# Versie_6.net
KiCad netlist of a schematic drawn in EAGLE
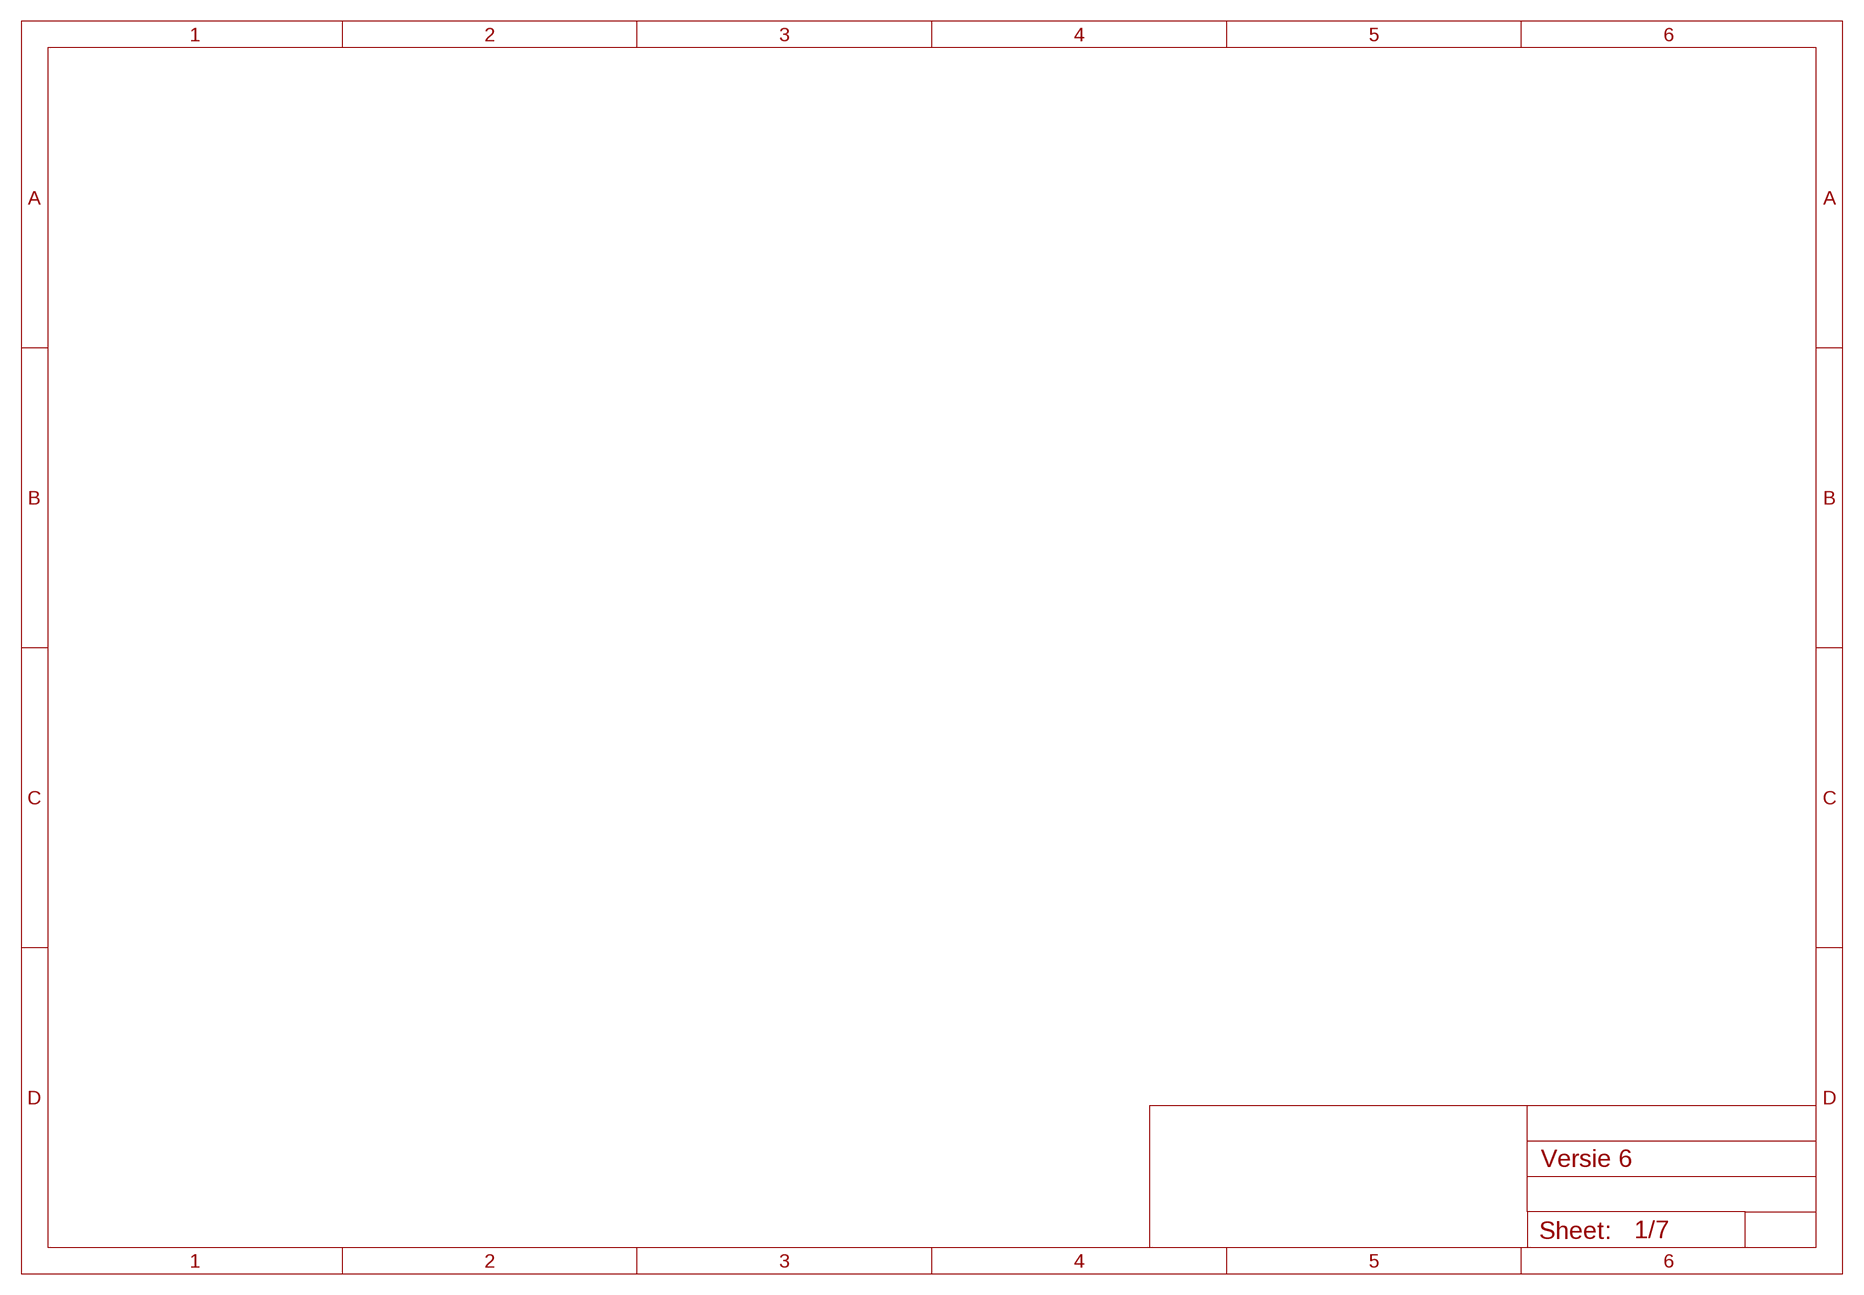
[diagram p0: schematic, sheet 1]
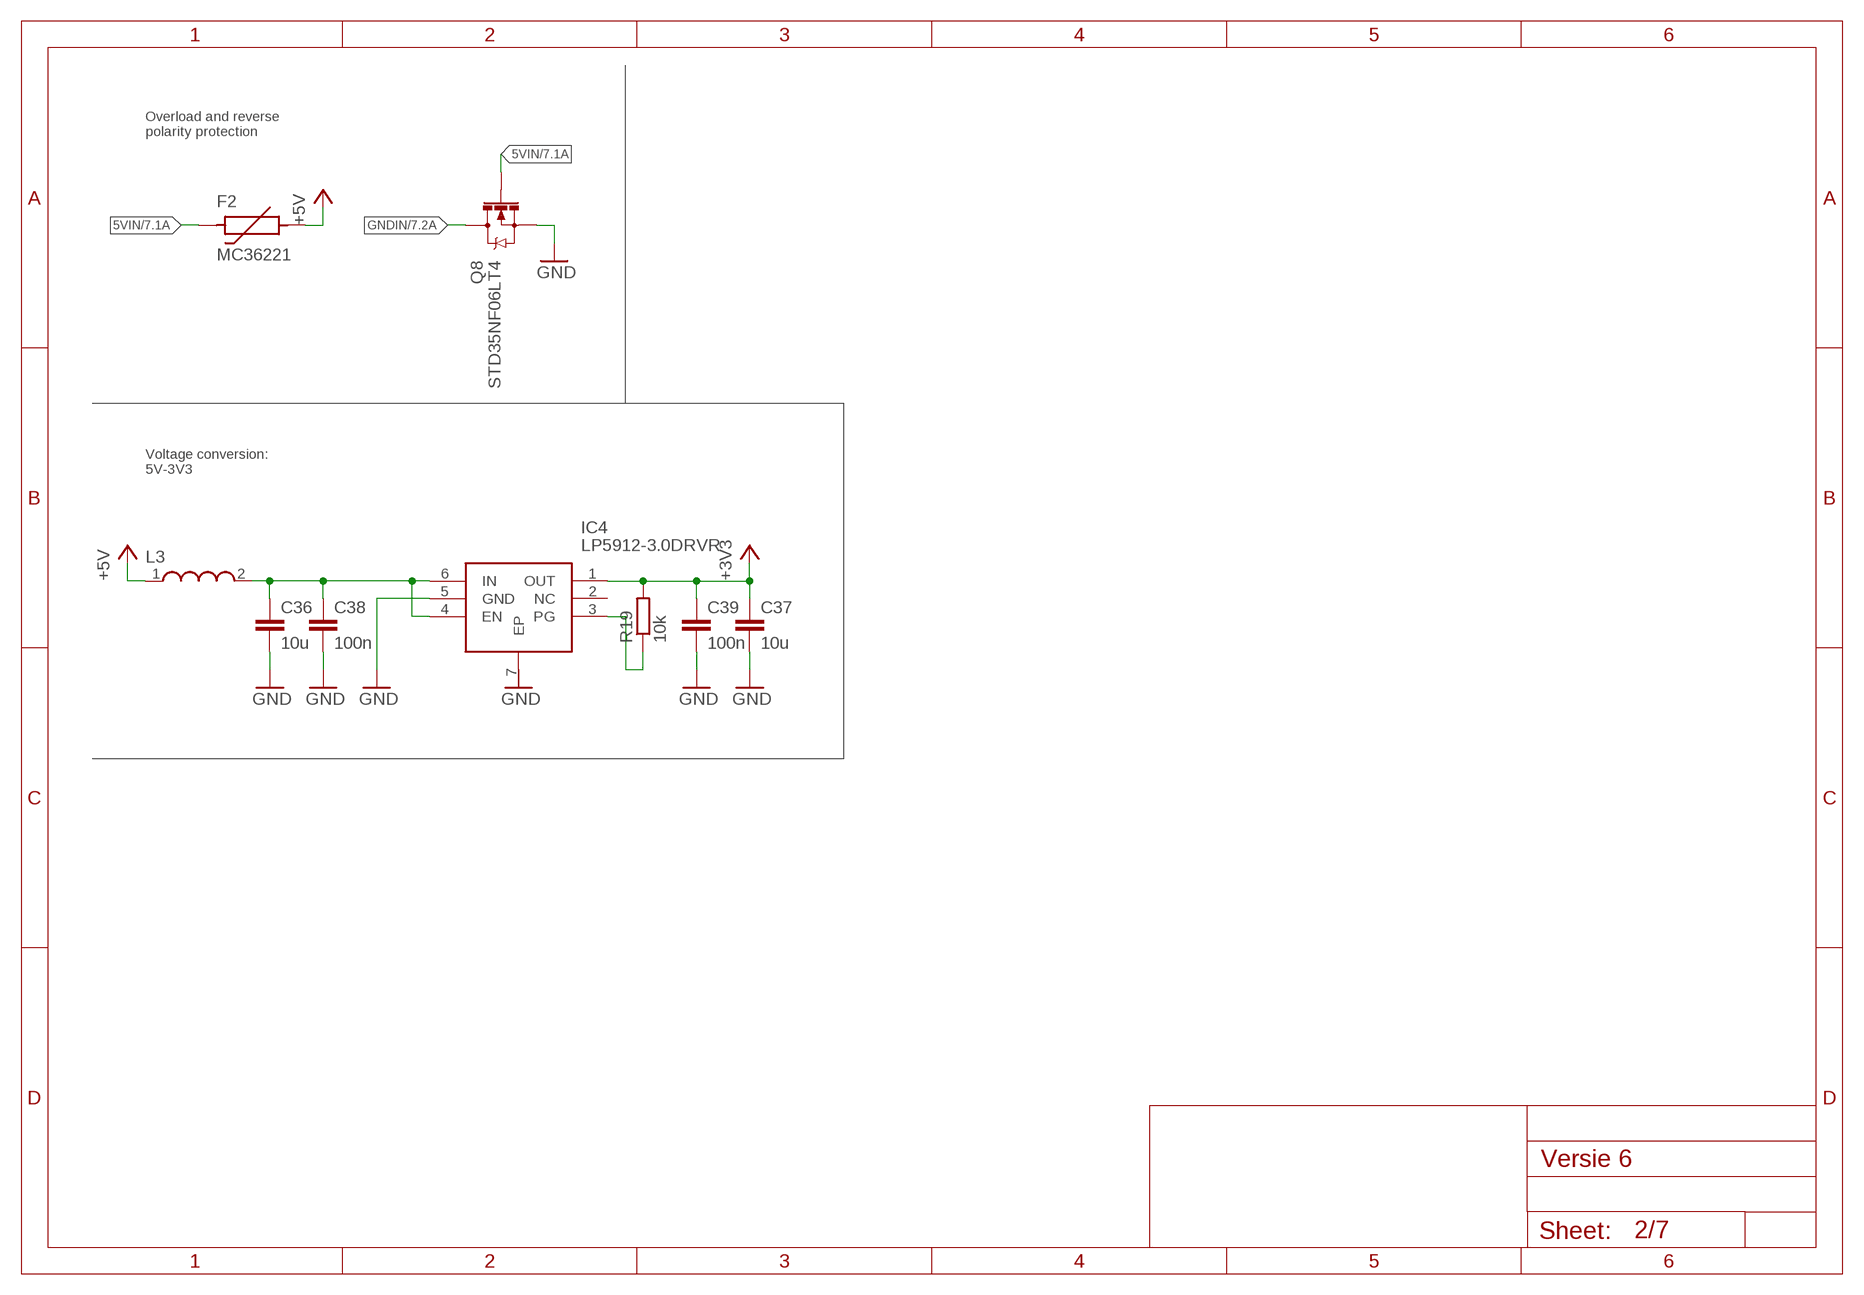
[diagram p1: schematic, sheet 2]
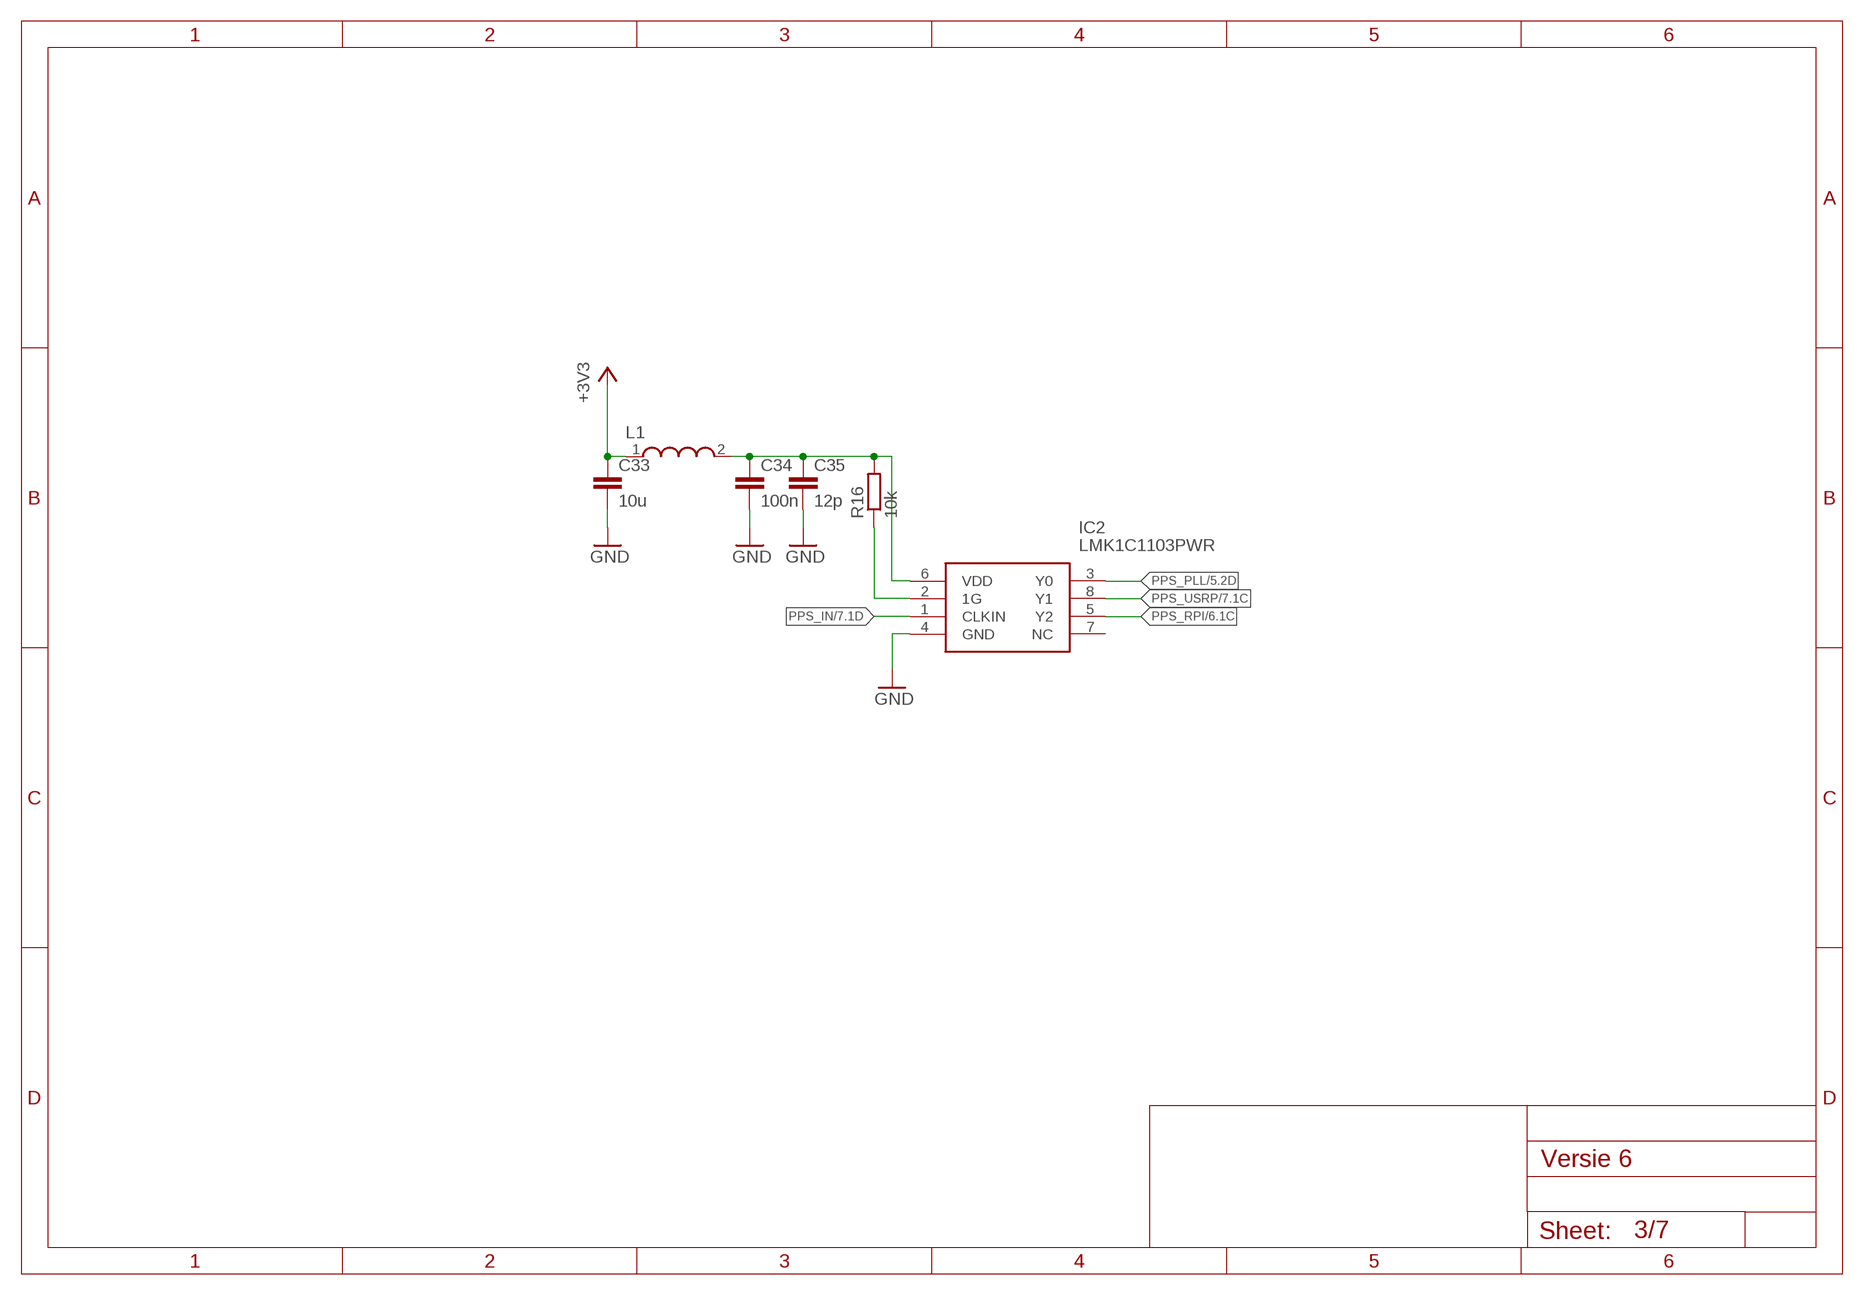
[diagram p2: schematic, sheet 3]
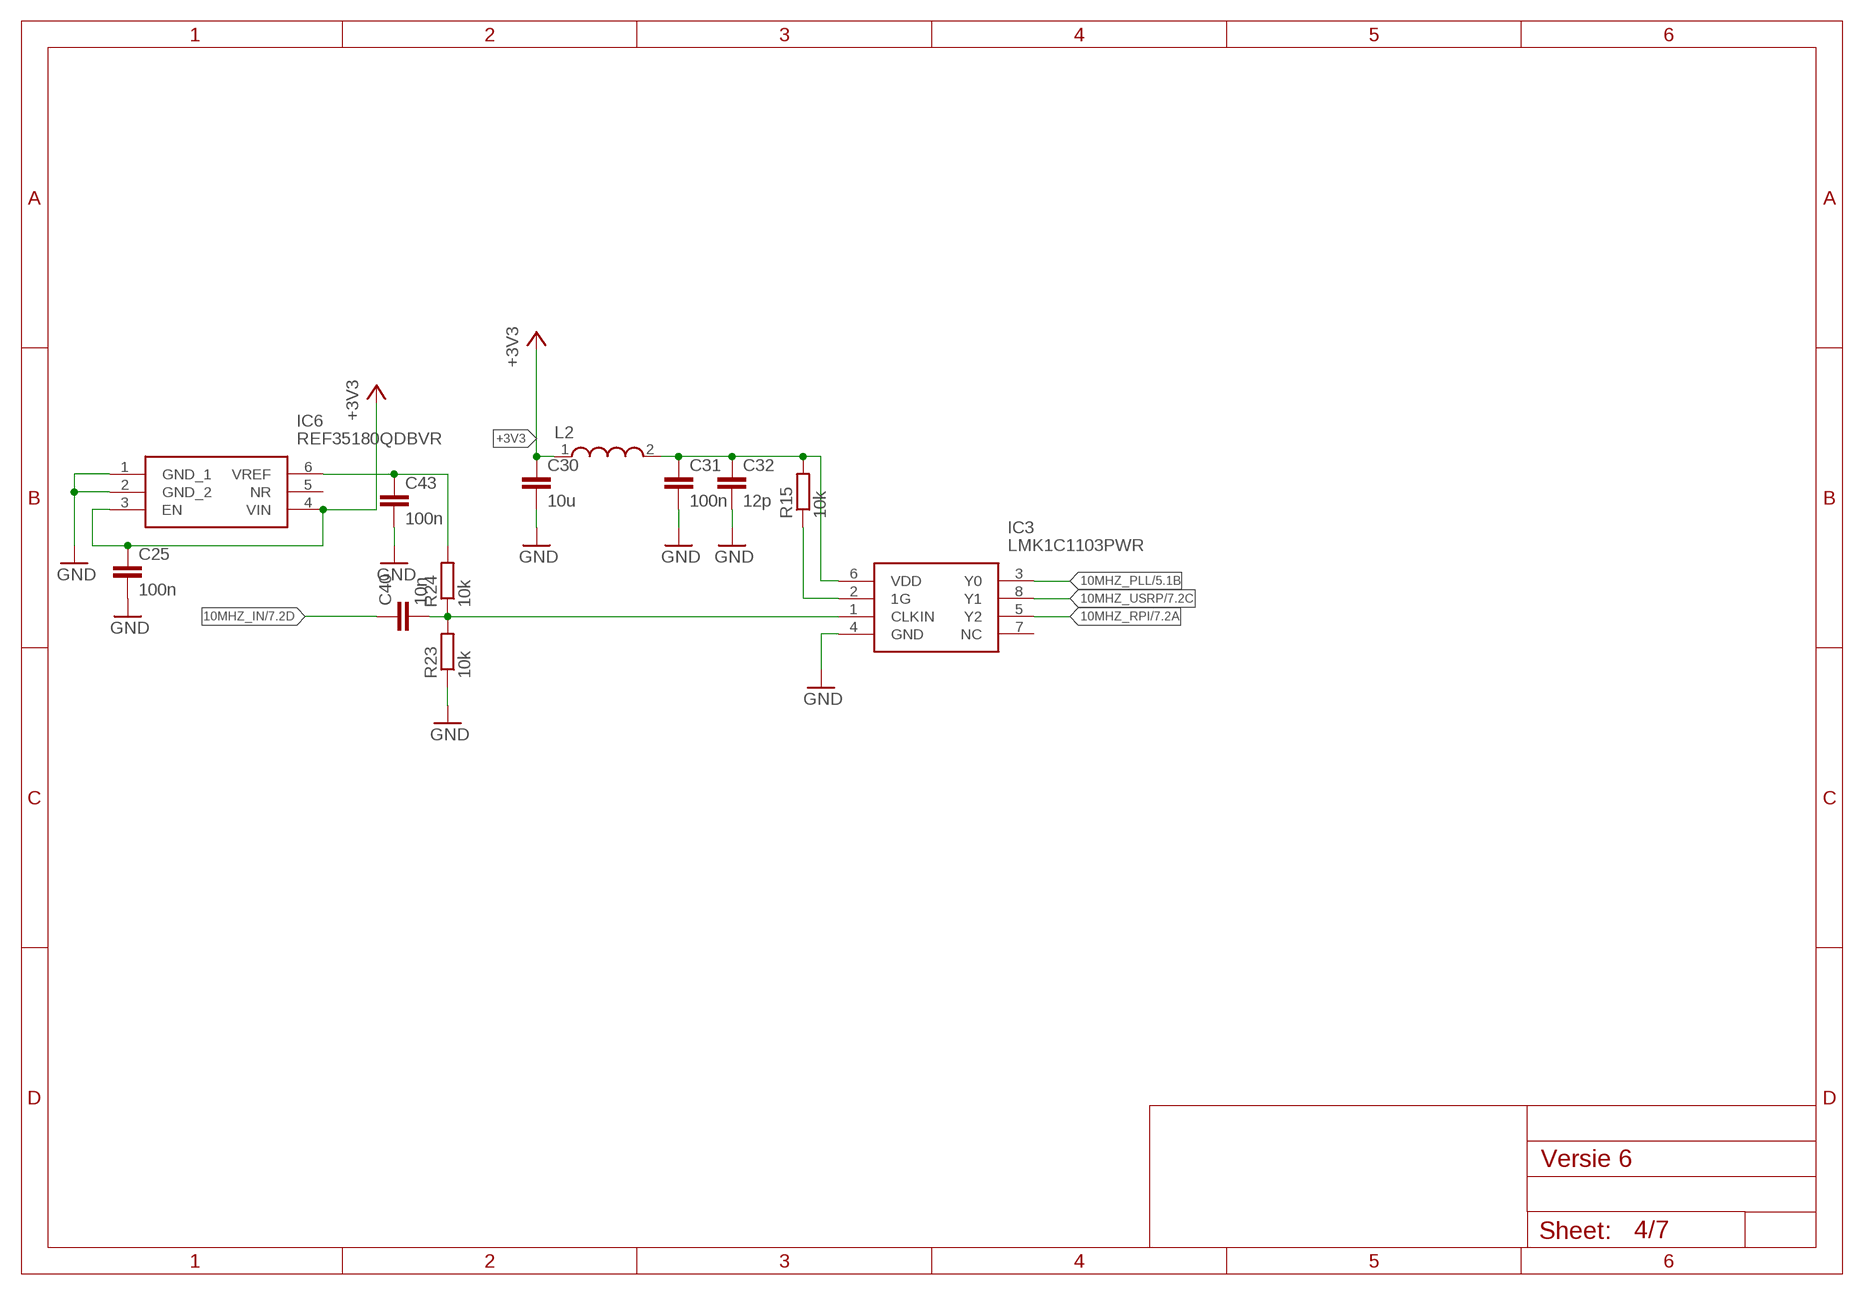
[diagram p3: schematic, sheet 4]
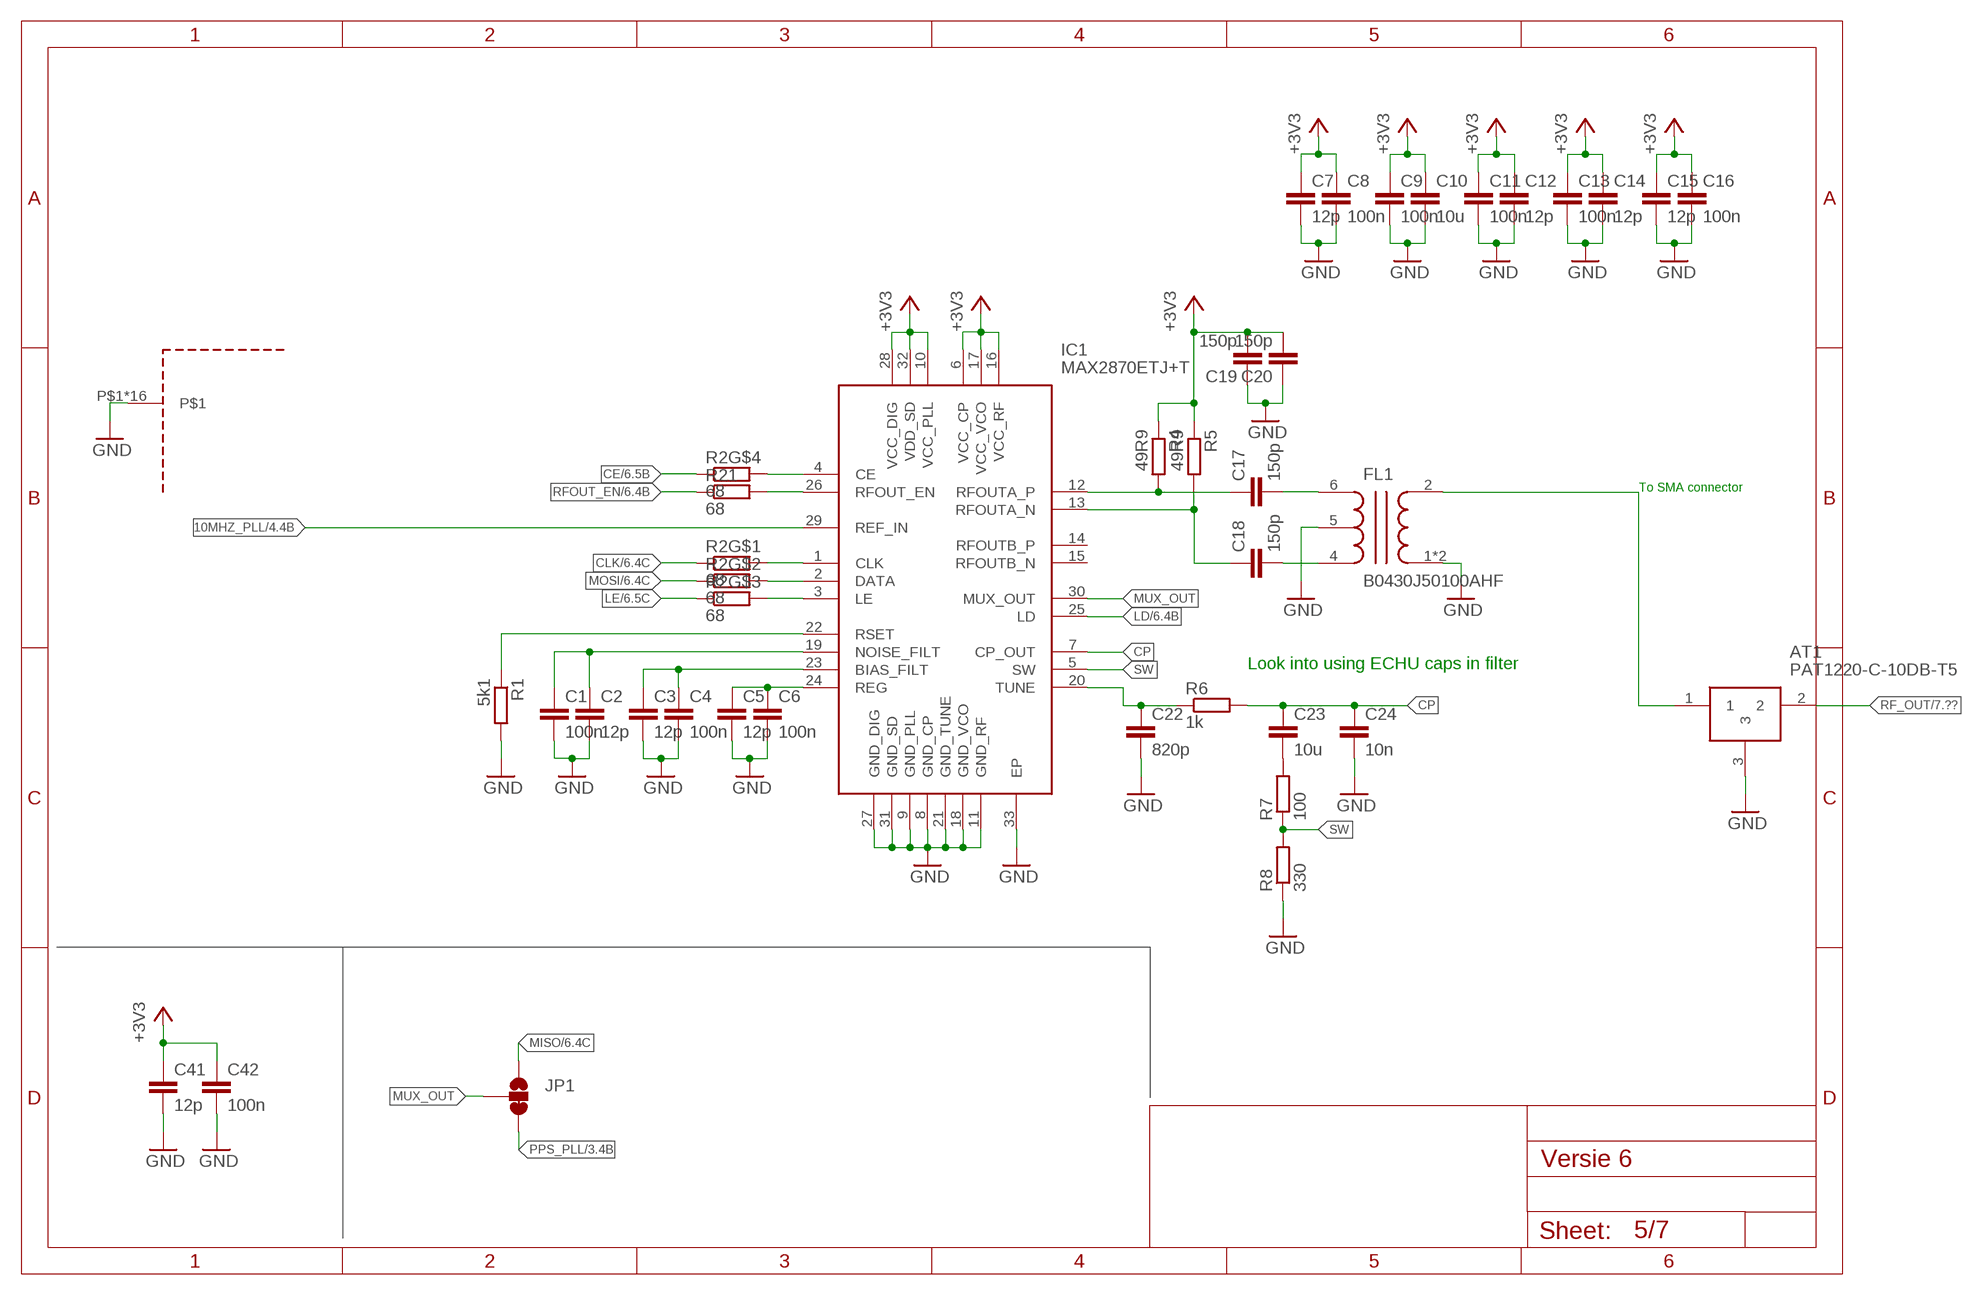
[diagram p4: schematic, sheet 5]
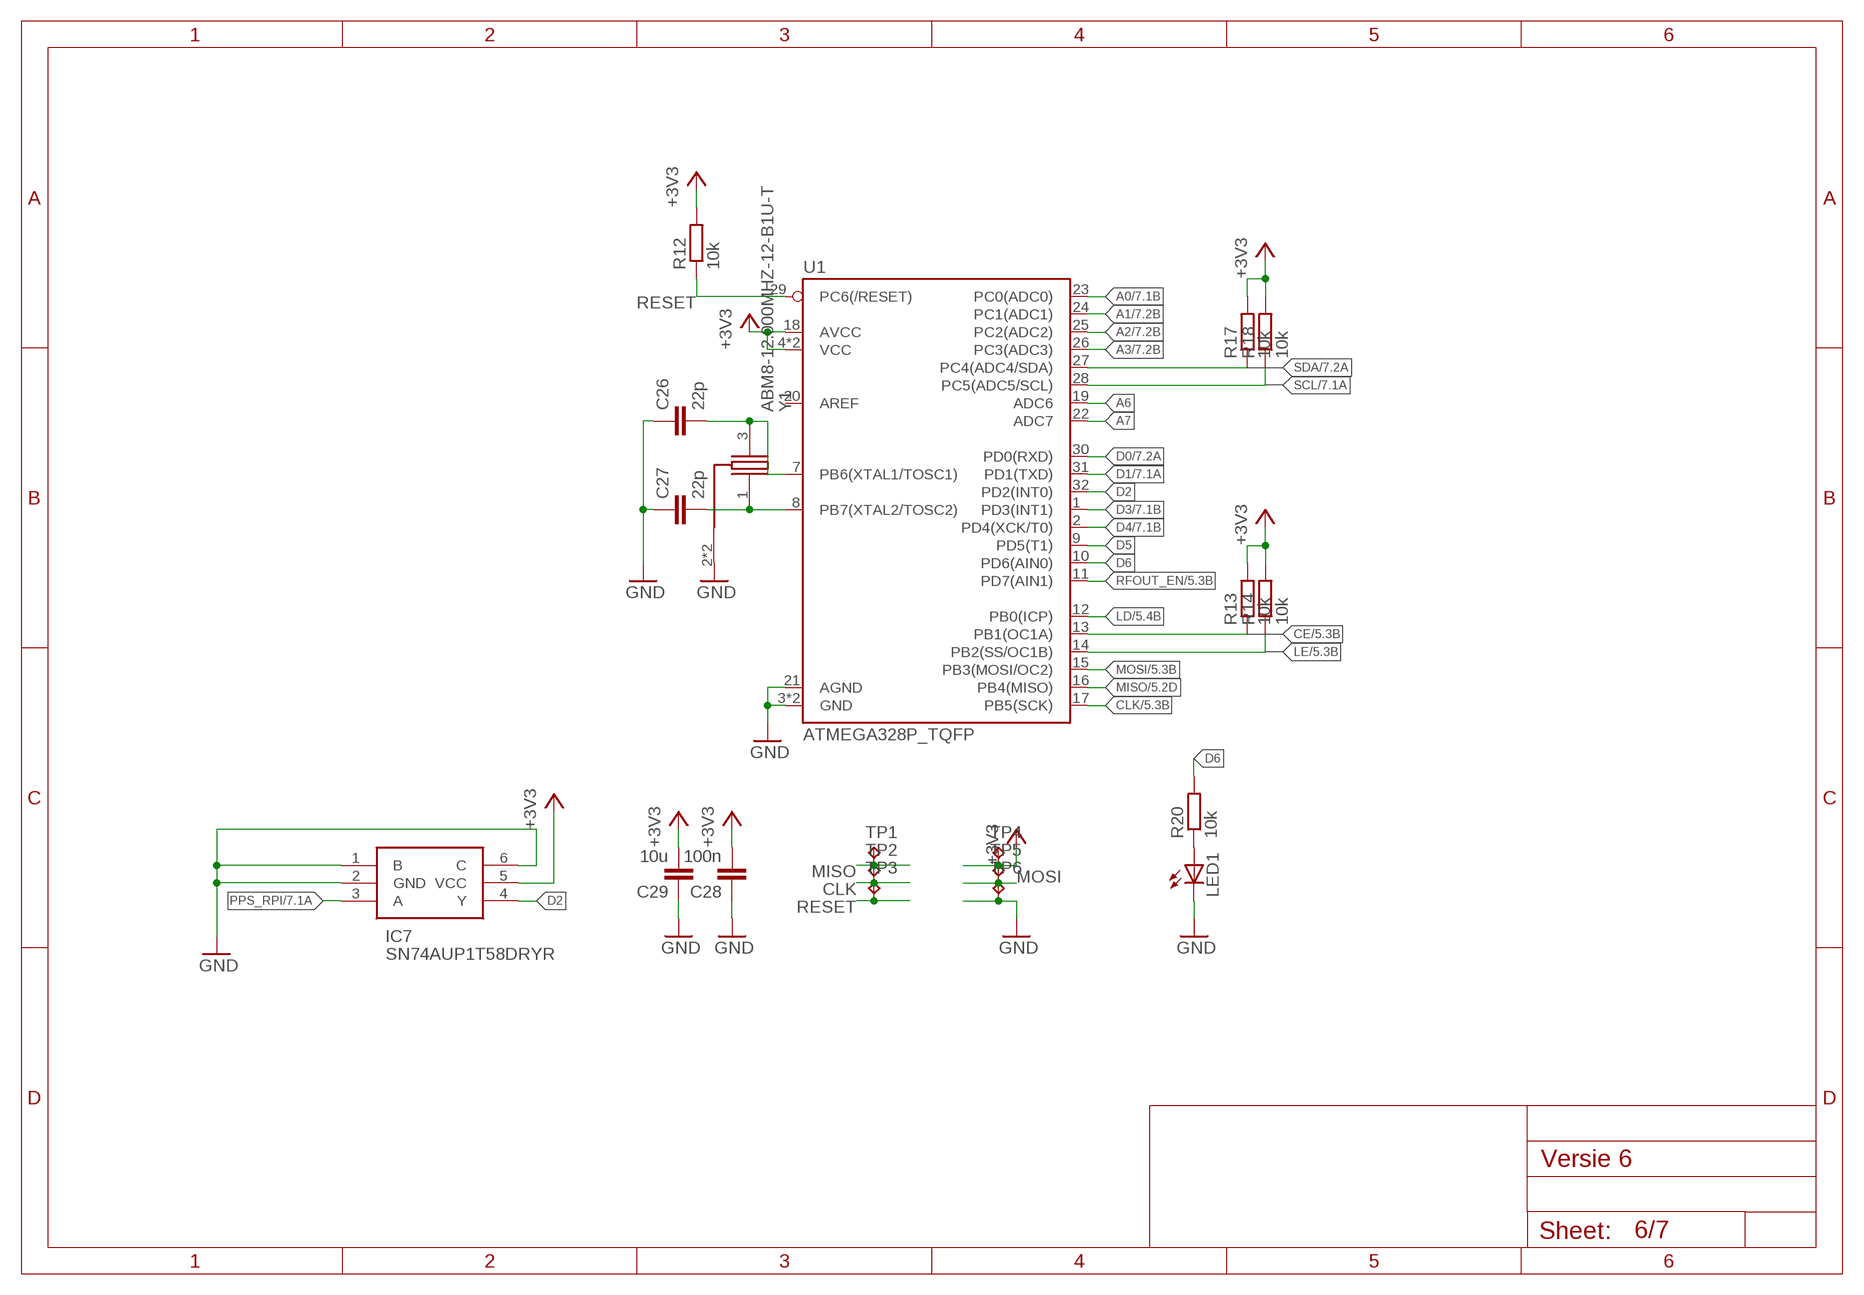
[diagram p5: schematic, sheet 6]
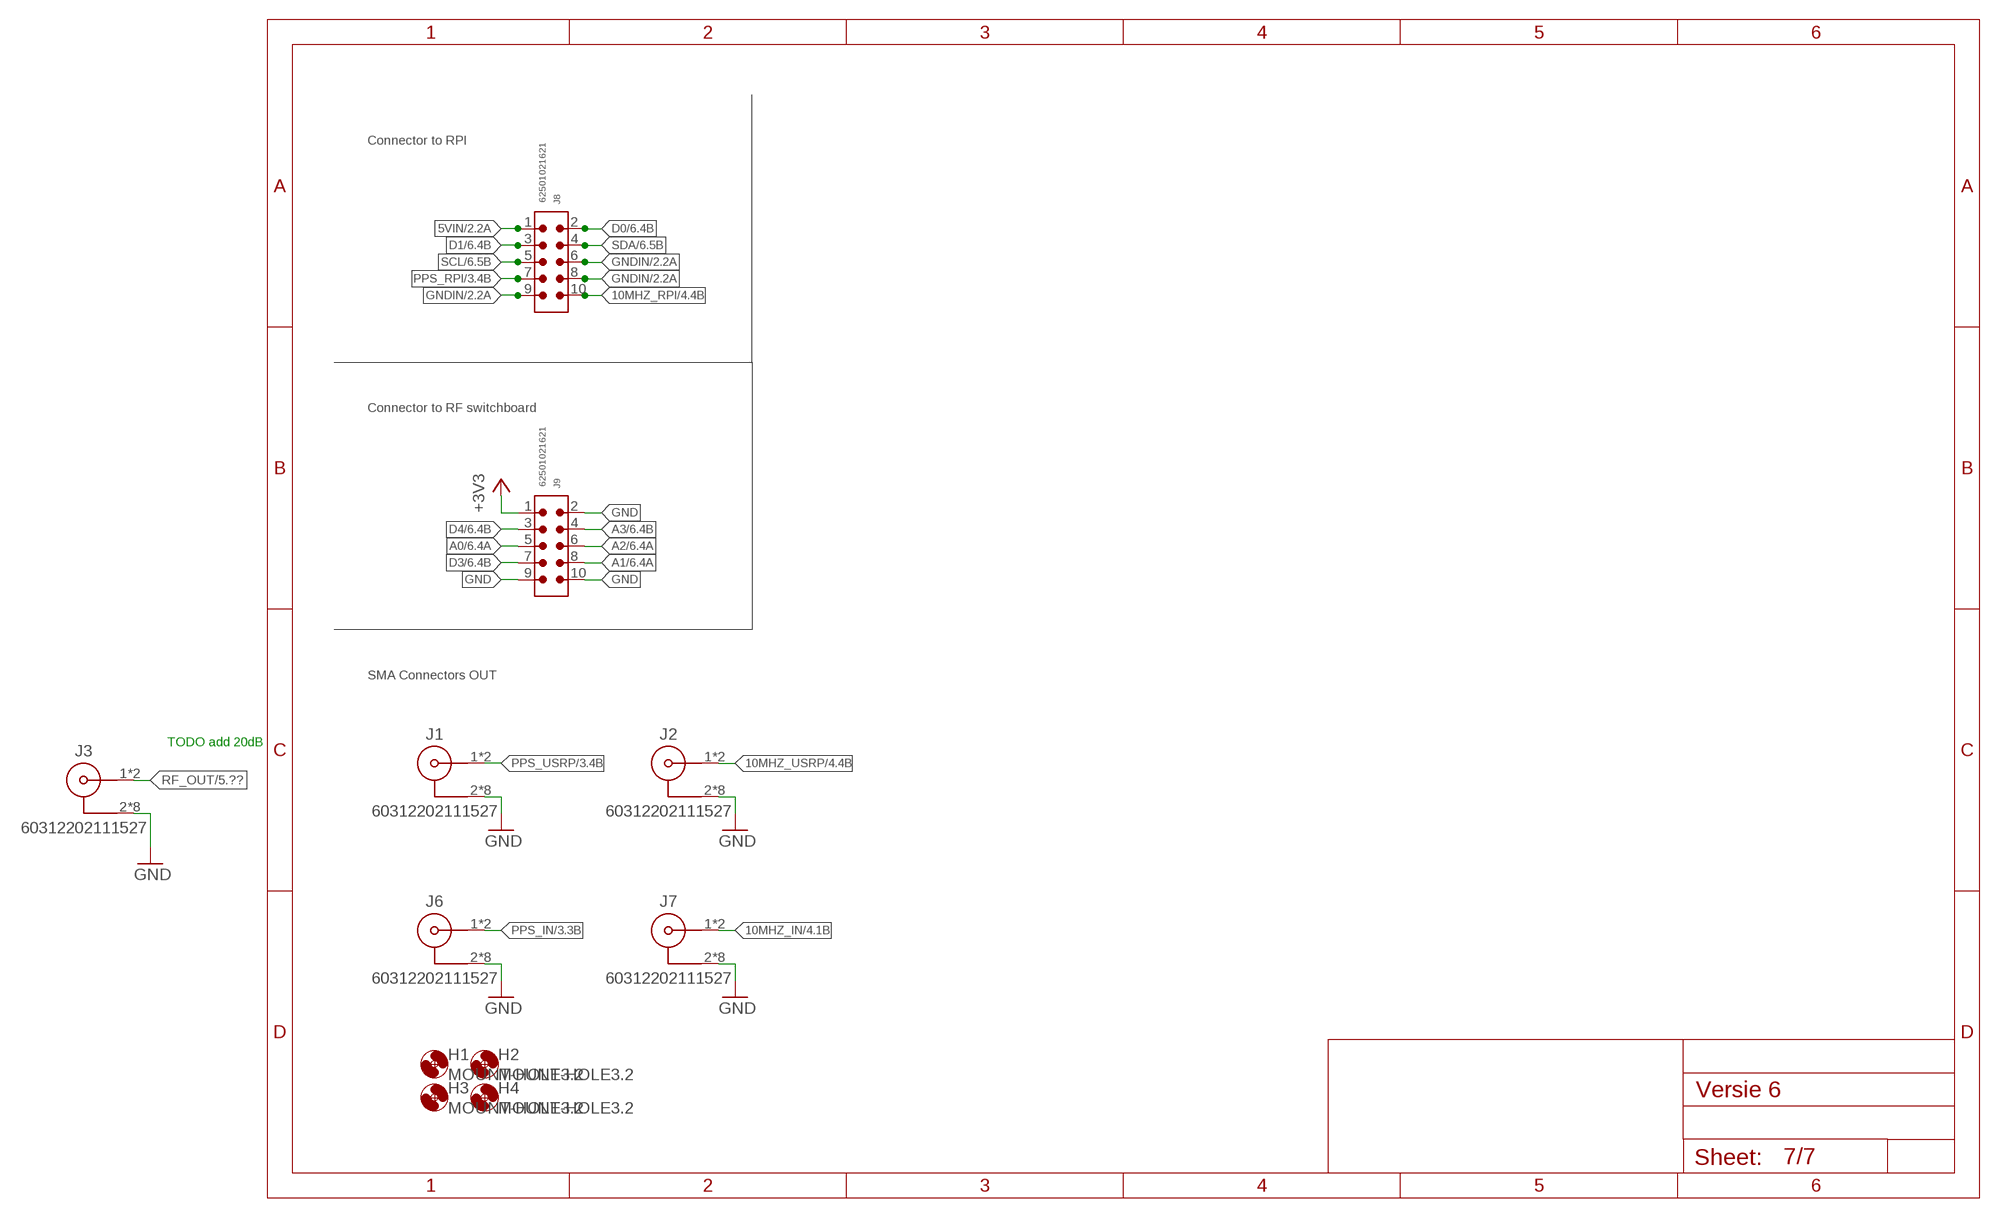
[diagram p6: schematic, sheet 7]

(export (version "E")
  (design (tool "Eeschema 10.0.6"))
  (components
    (comp (ref "C36")
      (value "10u")
      (footprint "eagle-import:C0603")
      (libsource (lib "eagle-import") (part "C-EUC0603"))
    )
    (comp (ref "C37")
      (value "10u")
      (footprint "eagle-import:C0603")
      (libsource (lib "eagle-import") (part "C-EUC0603"))
    )
    (comp (ref "C38")
      (value "100n")
      (footprint "eagle-import:C0603")
      (libsource (lib "eagle-import") (part "C-EUC0603"))
    )
    (comp (ref "C39")
      (value "100n")
      (footprint "eagle-import:C0603")
      (libsource (lib "eagle-import") (part "C-EUC0603"))
    )
    (comp (ref "F2")
      (value "MC36221")
      (footprint "eagle-import:1206")
      (libsource (lib "eagle-import") (part "MC36221"))
    )
    (comp (ref "IC4")
      (value "LP5912-3.0DRVR")
      (footprint "eagle-import:SON65P200X200X80-7N")
      (fields (field (name "MOUSER_PART_NUMBER") "595-LP5912-3.0DRVR"))
      (libsource (lib "eagle-import") (part "LP5912-3.0DRVR"))
    )
    (comp (ref "L3")
      (value "WE-CBA_0603(WB/HS)")
      (footprint "eagle-import:WE-CBA_0603(W=2.2)")
      (libsource (lib "eagle-import") (part "WE-CBA_0603(WB/HS)"))
    )
    (comp (ref "Q8")
      (value "STD35NF06LT4")
      (footprint "eagle-import:SOT23-3")
      (libsource (lib "eagle-import") (part "MOSFET-NCHANNEL_SOT23-3"))
    )
    (comp (ref "R19")
      (value "10k")
      (footprint "eagle-import:R0603")
      (libsource (lib "eagle-import") (part "R-EU_R0603"))
    )
    (comp (ref "H1")
      (value "MOUNT-HOLE3.2")
      (footprint "eagle-import:3,2")
      (libsource (lib "eagle-import") (part "MOUNT-HOLE3.2"))
    )
    (comp (ref "H2")
      (value "MOUNT-HOLE3.2")
      (footprint "eagle-import:3,2")
      (libsource (lib "eagle-import") (part "MOUNT-HOLE3.2"))
    )
    (comp (ref "H3")
      (value "MOUNT-HOLE3.2")
      (footprint "eagle-import:3,2")
      (libsource (lib "eagle-import") (part "MOUNT-HOLE3.2"))
    )
    (comp (ref "H4")
      (value "MOUNT-HOLE3.2")
      (footprint "eagle-import:3,2")
      (libsource (lib "eagle-import") (part "MOUNT-HOLE3.2"))
    )
    (comp (ref "J1")
      (value "60312202111527")
      (footprint "eagle-import:60312202111527")
      (libsource (lib "eagle-import") (part "60312202111527"))
    )
    (comp (ref "J2")
      (value "60312202111527")
      (footprint "eagle-import:60312202111527")
      (libsource (lib "eagle-import") (part "60312202111527"))
    )
    (comp (ref "J3")
      (value "60312202111527")
      (footprint "eagle-import:60312202111527")
      (libsource (lib "eagle-import") (part "60312202111527"))
    )
    (comp (ref "J6")
      (value "60312202111527")
      (footprint "eagle-import:60312202111527")
      (libsource (lib "eagle-import") (part "60312202111527"))
    )
    (comp (ref "J7")
      (value "60312202111527")
      (footprint "eagle-import:60312202111527")
      (libsource (lib "eagle-import") (part "60312202111527"))
    )
    (comp (ref "J8")
      (value "62501021621")
      (footprint "eagle-import:62501021621")
      (libsource (lib "eagle-import") (part "6250XX21621_62501021621"))
    )
    (comp (ref "J9")
      (value "62501021621")
      (footprint "eagle-import:62501021621")
      (libsource (lib "eagle-import") (part "6250XX21621_62501021621"))
    )
    (comp (ref "C25")
      (value "100n")
      (footprint "eagle-import:C0603")
      (libsource (lib "eagle-import") (part "C-EUC0603"))
    )
    (comp (ref "C30")
      (value "10u")
      (footprint "eagle-import:C0603")
      (libsource (lib "eagle-import") (part "C-EUC0603"))
    )
    (comp (ref "C31")
      (value "100n")
      (footprint "eagle-import:C0603")
      (libsource (lib "eagle-import") (part "C-EUC0603"))
    )
    (comp (ref "C32")
      (value "12p")
      (footprint "eagle-import:C0603")
      (libsource (lib "eagle-import") (part "C-EUC0603"))
    )
    (comp (ref "C40")
      (value "10n")
      (footprint "eagle-import:C0603")
      (libsource (lib "eagle-import") (part "C-EUC0603"))
    )
    (comp (ref "C43")
      (value "100n")
      (footprint "eagle-import:C0603")
      (libsource (lib "eagle-import") (part "C-EUC0603"))
    )
    (comp (ref "IC3")
      (value "LMK1C1103PWR")
      (footprint "eagle-import:SOP65P640X120-8N")
      (fields (field (name "MOUSER_PART_NUMBER") "595-LMK1C1103PWR"))
      (libsource (lib "eagle-import") (part "LMK1C1103PWR"))
    )
    (comp (ref "IC6")
      (value "REF35180QDBVR")
      (footprint "eagle-import:SOT95P280X145-6N")
      (fields (field (name "MOUSER_PART_NUMBER") "595-REF35180QDBVR"))
      (libsource (lib "eagle-import") (part "REF35180QDBVR"))
    )
    (comp (ref "L2")
      (value "WE-CBA_0603(WB/HS)")
      (footprint "eagle-import:WE-CBA_0603(W=2.2)")
      (libsource (lib "eagle-import") (part "WE-CBA_0603(WB/HS)"))
    )
    (comp (ref "R15")
      (value "10k")
      (footprint "eagle-import:R0603")
      (libsource (lib "eagle-import") (part "R-EU_R0603"))
    )
    (comp (ref "R23")
      (value "10k")
      (footprint "eagle-import:R0603")
      (libsource (lib "eagle-import") (part "R-EU_R0603"))
    )
    (comp (ref "R24")
      (value "10k")
      (footprint "eagle-import:R0603")
      (libsource (lib "eagle-import") (part "R-EU_R0603"))
    )
    (comp (ref "C26")
      (value "22p")
      (footprint "eagle-import:C0603")
      (libsource (lib "eagle-import") (part "C-EUC0603"))
    )
    (comp (ref "C27")
      (value "22p")
      (footprint "eagle-import:C0603")
      (libsource (lib "eagle-import") (part "C-EUC0603"))
    )
    (comp (ref "C28")
      (value "100n")
      (footprint "eagle-import:C0603")
      (libsource (lib "eagle-import") (part "C-EUC0603"))
    )
    (comp (ref "C29")
      (value "10u")
      (footprint "eagle-import:C0603")
      (libsource (lib "eagle-import") (part "C-EUC0603"))
    )
    (comp (ref "IC7")
      (value "SN74AUP1T58DRYR")
      (footprint "eagle-import:SON50P100X145X60-6N")
      (libsource (lib "eagle-import") (part "SN74AUP1T58DRYR"))
    )
    (comp (ref "LED1")
      (value "LEDCHIPLED_0805")
      (footprint "eagle-import:CHIPLED_0805")
      (libsource (lib "eagle-import") (part "LEDCHIPLED_0805"))
    )
    (comp (ref "R12")
      (value "10k")
      (footprint "eagle-import:R0603")
      (libsource (lib "eagle-import") (part "R-EU_R0603"))
    )
    (comp (ref "R13")
      (value "10k")
      (footprint "eagle-import:R0603")
      (libsource (lib "eagle-import") (part "R-EU_R0603"))
    )
    (comp (ref "R14")
      (value "10k")
      (footprint "eagle-import:R0603")
      (libsource (lib "eagle-import") (part "R-EU_R0603"))
    )
    (comp (ref "R17")
      (value "10k")
      (footprint "eagle-import:R0603")
      (libsource (lib "eagle-import") (part "R-EU_R0603"))
    )
    (comp (ref "R18")
      (value "10k")
      (footprint "eagle-import:R0603")
      (libsource (lib "eagle-import") (part "R-EU_R0603"))
    )
    (comp (ref "R20")
      (value "10k")
      (footprint "eagle-import:R0603")
      (libsource (lib "eagle-import") (part "R-EU_R0603"))
    )
    (comp (ref "TP1")
      (value "TPTP16R")
      (footprint "eagle-import:TP16R")
      (libsource (lib "eagle-import") (part "TPTP16R"))
    )
    (comp (ref "TP2")
      (value "TPTP16R")
      (footprint "eagle-import:TP16R")
      (libsource (lib "eagle-import") (part "TPTP16R"))
    )
    (comp (ref "TP3")
      (value "TPTP16R")
      (footprint "eagle-import:TP16R")
      (libsource (lib "eagle-import") (part "TPTP16R"))
    )
    (comp (ref "TP4")
      (value "TPTP16R")
      (footprint "eagle-import:TP16R")
      (libsource (lib "eagle-import") (part "TPTP16R"))
    )
    (comp (ref "TP5")
      (value "TPTP16R")
      (footprint "eagle-import:TP16R")
      (libsource (lib "eagle-import") (part "TPTP16R"))
    )
    (comp (ref "TP6")
      (value "TPTP16R")
      (footprint "eagle-import:TP16R")
      (libsource (lib "eagle-import") (part "TPTP16R"))
    )
    (comp (ref "U1")
      (value "ATMEGA328P_TQFP")
      (footprint "eagle-import:TQFP32-08")
      (libsource (lib "eagle-import") (part "ATMEGA328P_TQFP"))
    )
    (comp (ref "Y1")
      (value "ABM8-12.000MHZ-12-B1U-T")
      (footprint "eagle-import:ABM810000MHZ12D2W")
      (fields (field (name "MOUSER_PART_NUMBER") "815-M812000MHZ12B1UT"))
      (libsource (lib "eagle-import") (part "ABM8-12.000MHZ-12-B1U-T"))
    )
    (comp (ref "AT1")
      (value "PAT1220-C-10DB-T5")
      (footprint "eagle-import:PAT1220C10DBT5")
      (fields (field (name "MOUSER_PART_NUMBER") "754-PAT1220C10DBT5"))
      (libsource (lib "eagle-import") (part "PAT1220-C-10DB-T5"))
    )
    (comp (ref "C1")
      (value "100n")
      (footprint "eagle-import:C0603")
      (libsource (lib "eagle-import") (part "C-EUC0603"))
    )
    (comp (ref "C2")
      (value "12p")
      (footprint "eagle-import:C0603")
      (libsource (lib "eagle-import") (part "C-EUC0603"))
    )
    (comp (ref "C3")
      (value "12p")
      (footprint "eagle-import:C0603")
      (libsource (lib "eagle-import") (part "C-EUC0603"))
    )
    (comp (ref "C4")
      (value "100n")
      (footprint "eagle-import:C0603")
      (libsource (lib "eagle-import") (part "C-EUC0603"))
    )
    (comp (ref "C5")
      (value "12p")
      (footprint "eagle-import:C0603")
      (libsource (lib "eagle-import") (part "C-EUC0603"))
    )
    (comp (ref "C6")
      (value "100n")
      (footprint "eagle-import:C0603")
      (libsource (lib "eagle-import") (part "C-EUC0603"))
    )
    (comp (ref "C7")
      (value "12p")
      (footprint "eagle-import:C0603")
      (libsource (lib "eagle-import") (part "C-EUC0603"))
    )
    (comp (ref "C8")
      (value "100n")
      (footprint "eagle-import:C0603")
      (libsource (lib "eagle-import") (part "C-EUC0603"))
    )
    (comp (ref "C9")
      (value "100n")
      (footprint "eagle-import:C0603")
      (libsource (lib "eagle-import") (part "C-EUC0603"))
    )
    (comp (ref "C10")
      (value "10u")
      (footprint "eagle-import:C0603")
      (libsource (lib "eagle-import") (part "C-EUC0603"))
    )
    (comp (ref "C11")
      (value "100n")
      (footprint "eagle-import:C0603")
      (libsource (lib "eagle-import") (part "C-EUC0603"))
    )
    (comp (ref "C12")
      (value "12p")
      (footprint "eagle-import:C0603")
      (libsource (lib "eagle-import") (part "C-EUC0603"))
    )
    (comp (ref "C13")
      (value "100n")
      (footprint "eagle-import:C0603")
      (libsource (lib "eagle-import") (part "C-EUC0603"))
    )
    (comp (ref "C14")
      (value "12p")
      (footprint "eagle-import:C0603")
      (libsource (lib "eagle-import") (part "C-EUC0603"))
    )
    (comp (ref "C15")
      (value "12p")
      (footprint "eagle-import:C0603")
      (libsource (lib "eagle-import") (part "C-EUC0603"))
    )
    (comp (ref "C16")
      (value "100n")
      (footprint "eagle-import:C0603")
      (libsource (lib "eagle-import") (part "C-EUC0603"))
    )
    (comp (ref "C17")
      (value "150p")
      (footprint "eagle-import:C0402")
      (libsource (lib "eagle-import") (part "C-EUC0402"))
    )
    (comp (ref "C18")
      (value "150p")
      (footprint "eagle-import:C0402")
      (libsource (lib "eagle-import") (part "C-EUC0402"))
    )
    (comp (ref "C19")
      (value "150p")
      (footprint "eagle-import:C0402")
      (libsource (lib "eagle-import") (part "C-EUC0402"))
    )
    (comp (ref "C20")
      (value "150p")
      (footprint "eagle-import:C0402")
      (libsource (lib "eagle-import") (part "C-EUC0402"))
    )
    (comp (ref "C22")
      (value "820p")
      (footprint "eagle-import:C0603")
      (libsource (lib "eagle-import") (part "C-EUC0603"))
    )
    (comp (ref "C23")
      (value "10u")
      (footprint "eagle-import:C0603")
      (libsource (lib "eagle-import") (part "C-EUC0603"))
    )
    (comp (ref "C24")
      (value "10n")
      (footprint "eagle-import:C0603")
      (libsource (lib "eagle-import") (part "C-EUC0603"))
    )
    (comp (ref "C41")
      (value "12p")
      (footprint "eagle-import:C0603")
      (libsource (lib "eagle-import") (part "C-EUC0603"))
    )
    (comp (ref "C42")
      (value "100n")
      (footprint "eagle-import:C0603")
      (libsource (lib "eagle-import") (part "C-EUC0603"))
    )
    (comp (ref "FL1")
      (value "B0430J50100AHF")
      (footprint "eagle-import:B0430J50100AHF")
      (fields (field (name "MOUSER_PART_NUMBER") "620-B0430J50100AHF"))
      (libsource (lib "eagle-import") (part "B0430J50100AHF"))
    )
    (comp (ref "IC1")
      (value "MAX2870ETJ+T")
      (footprint "eagle-import:QFN50P500X500X80-33N")
      (fields (field (name "MOUSER_PART_NUMBER") "700-MAX2870ETJ+T"))
      (libsource (lib "eagle-import") (part "MAX2870ETJ+T"))
    )
    (comp (ref "JP1")
      (value "JUMPER-SMT_3_1-NC_TRACE_SILK")
      (footprint "eagle-import:SMT-JUMPER_3_1-NC_TRACE_SILK")
      (libsource (lib "eagle-import") (part "JUMPER-SMT_3_1-NC_TRACE_SILK"))
    )
    (comp (ref "R1")
      (value "5k1")
      (footprint "eagle-import:R0603")
      (libsource (lib "eagle-import") (part "R-EU_R0603"))
    )
    (comp (ref "R2")
      (value "68")
      (footprint "eagle-import:CAY16A1003F4LF")
      (fields
        (field (name "MANUFACTURER_PART_NUMBER") "CAY16A-2002F4LF")
        (field (name "MOUSER_PART_NUMBER") "652-CAY16A-2002F4LF")
      )
      (libsource (lib "eagle-import") (part "CAY16A-2002F4LF"))
    )
    (comp (ref "R4")
      (value "49R9")
      (footprint "eagle-import:R0402")
      (libsource (lib "eagle-import") (part "R-EU_R0402"))
    )
    (comp (ref "R5")
      (value "49R9")
      (footprint "eagle-import:R0402")
      (libsource (lib "eagle-import") (part "R-EU_R0402"))
    )
    (comp (ref "R6")
      (value "1k")
      (footprint "eagle-import:R0603")
      (libsource (lib "eagle-import") (part "R-EU_R0603"))
    )
    (comp (ref "R7")
      (value "100")
      (footprint "eagle-import:R0603")
      (libsource (lib "eagle-import") (part "R-EU_R0603"))
    )
    (comp (ref "R8")
      (value "330")
      (footprint "eagle-import:R0603")
      (libsource (lib "eagle-import") (part "R-EU_R0603"))
    )
    (comp (ref "R21")
      (value "68")
      (footprint "eagle-import:R0603")
      (libsource (lib "eagle-import") (part "R-EU_R0603"))
    )
    (comp (ref "U$1")
      (value "BMI-S-209-F-20-R")
      (footprint "eagle-import:BMI-S-209-F-20-R")
      (libsource (lib "eagle-import") (part "BMI-S-209-F-20-R"))
    )
    (comp (ref "C33")
      (value "10u")
      (footprint "eagle-import:C0603")
      (libsource (lib "eagle-import") (part "C-EUC0603"))
    )
    (comp (ref "C34")
      (value "100n")
      (footprint "eagle-import:C0603")
      (libsource (lib "eagle-import") (part "C-EUC0603"))
    )
    (comp (ref "C35")
      (value "12p")
      (footprint "eagle-import:C0603")
      (libsource (lib "eagle-import") (part "C-EUC0603"))
    )
    (comp (ref "IC2")
      (value "LMK1C1103PWR")
      (footprint "eagle-import:SOP65P640X120-8N")
      (fields (field (name "MOUSER_PART_NUMBER") "595-LMK1C1103PWR"))
      (libsource (lib "eagle-import") (part "LMK1C1103PWR"))
    )
    (comp (ref "L1")
      (value "WE-CBA_0603(WB/HS)")
      (footprint "eagle-import:WE-CBA_0603(W=2.2)")
      (libsource (lib "eagle-import") (part "WE-CBA_0603(WB/HS)"))
    )
    (comp (ref "R16")
      (value "10k")
      (footprint "eagle-import:R0603")
      (libsource (lib "eagle-import") (part "R-EU_R0603"))
    )
  )
  (nets
    (net (code "1") (name "+3V3") (class "Default")
      (node (ref "C10") (pin "1") (pinfunction "1_1") (pintype "passive"))
      (node (ref "C11") (pin "1") (pinfunction "1_1") (pintype "passive"))
      (node (ref "C12") (pin "1") (pinfunction "1_1") (pintype "passive"))
      (node (ref "C13") (pin "1") (pinfunction "1_1") (pintype "passive"))
      (node (ref "C14") (pin "1") (pinfunction "1_1") (pintype "passive"))
      (node (ref "C15") (pin "1") (pinfunction "1_1") (pintype "passive"))
      (node (ref "C16") (pin "1") (pinfunction "1_1") (pintype "passive"))
      (node (ref "C19") (pin "2") (pinfunction "2_2") (pintype "passive"))
      (node (ref "C20") (pin "2") (pinfunction "2_2") (pintype "passive"))
      (node (ref "C25") (pin "1") (pinfunction "1_1") (pintype "passive"))
      (node (ref "C28") (pin "2") (pinfunction "2_2") (pintype "passive"))
      (node (ref "C29") (pin "2") (pinfunction "2_2") (pintype "passive"))
      (node (ref "C30") (pin "1") (pinfunction "1_1") (pintype "passive"))
      (node (ref "C33") (pin "1") (pinfunction "1_1") (pintype "passive"))
      (node (ref "C37") (pin "1") (pinfunction "1_1") (pintype "passive"))
      (node (ref "C39") (pin "1") (pinfunction "1_1") (pintype "passive"))
      (node (ref "C41") (pin "1") (pinfunction "1_1") (pintype "passive"))
      (node (ref "C42") (pin "1") (pinfunction "1_1") (pintype "passive"))
      (node (ref "C7") (pin "1") (pinfunction "1_1") (pintype "passive"))
      (node (ref "C8") (pin "1") (pinfunction "1_1") (pintype "passive"))
      (node (ref "C9") (pin "1") (pinfunction "1_1") (pintype "passive"))
      (node (ref "IC1") (pin "10") (pinfunction "VCC_PLL_10") (pintype "bidirectional"))
      (node (ref "IC1") (pin "16") (pinfunction "VCC_RF_16") (pintype "bidirectional"))
      (node (ref "IC1") (pin "17") (pinfunction "VCC_VCO_17") (pintype "bidirectional"))
      (node (ref "IC1") (pin "28") (pinfunction "VCC_DIG_28") (pintype "bidirectional"))
      (node (ref "IC1") (pin "32") (pinfunction "VDD_SD_32") (pintype "bidirectional"))
      (node (ref "IC1") (pin "6") (pinfunction "VCC_CP_6") (pintype "bidirectional"))
      (node (ref "IC4") (pin "1") (pinfunction "OUT_1") (pintype "bidirectional"))
      (node (ref "IC6") (pin "3") (pinfunction "EN_3") (pintype "bidirectional"))
      (node (ref "IC6") (pin "4") (pinfunction "VIN_4") (pintype "bidirectional"))
      (node (ref "IC7") (pin "5") (pinfunction "VCC_5") (pintype "bidirectional"))
      (node (ref "J9") (pin "1") (pinfunction "1_1") (pintype "passive"))
      (node (ref "L1") (pin "1") (pinfunction "1_1") (pintype "passive"))
      (node (ref "L2") (pin "1") (pinfunction "1_1") (pintype "passive"))
      (node (ref "R12") (pin "2") (pinfunction "2_2") (pintype "passive"))
      (node (ref "R13") (pin "2") (pinfunction "2_2") (pintype "passive"))
      (node (ref "R14") (pin "2") (pinfunction "2_2") (pintype "passive"))
      (node (ref "R17") (pin "2") (pinfunction "2_2") (pintype "passive"))
      (node (ref "R18") (pin "2") (pinfunction "2_2") (pintype "passive"))
      (node (ref "R19") (pin "2") (pinfunction "2_2") (pintype "passive"))
      (node (ref "R4") (pin "1") (pinfunction "1_1") (pintype "passive"))
      (node (ref "R5") (pin "1") (pinfunction "1_1") (pintype "passive"))
      (node (ref "TP4") (pin "TP") (pinfunction "TP_TP") (pintype "input"))
      (node (ref "U1") (pin "18") (pinfunction "AVCC_18") (pintype "bidirectional"))
      (node (ref "U1") (pin "4") (pinfunction "VCC_4") (pintype "bidirectional"))
      (node (ref "U1") (pin "6") (pinfunction "VCC_6") (pintype "bidirectional"))
    )
    (net (code "2") (name "+5V") (class "Default")
      (node (ref "F2") (pin "P$2") (pinfunction "P$2_P$2") (pintype "bidirectional"))
      (node (ref "L3") (pin "1") (pinfunction "1_1") (pintype "passive"))
    )
    (net (code "3") (name "5VIN") (class "Default")
      (node (ref "F2") (pin "P$1") (pinfunction "P$1_P$1") (pintype "bidirectional"))
      (node (ref "J8") (pin "1") (pinfunction "1_1") (pintype "passive"))
      (node (ref "Q8") (pin "1") (pinfunction "G_1") (pintype "passive"))
    )
    (net (code "4") (name "10MHZ_IN") (class "Default")
      (node (ref "C40") (pin "1") (pinfunction "1_1") (pintype "passive"))
      (node (ref "J7") (pin "1") (pinfunction "1_1") (pintype "passive"))
      (node (ref "J7") (pin "6") (pinfunction "1_6") (pintype "passive"))
    )
    (net (code "5") (name "10MHZ_PLL") (class "Default")
      (node (ref "IC1") (pin "29") (pinfunction "REF_IN_29") (pintype "bidirectional"))
      (node (ref "IC3") (pin "3") (pinfunction "Y0_3") (pintype "bidirectional"))
    )
    (net (code "6") (name "10MHZ_RPI") (class "Default")
      (node (ref "IC3") (pin "5") (pinfunction "Y2_5") (pintype "bidirectional"))
      (node (ref "J8") (pin "10") (pinfunction "10_10") (pintype "passive"))
    )
    (net (code "7") (name "10MHZ_USRP") (class "Default")
      (node (ref "IC3") (pin "8") (pinfunction "Y1_8") (pintype "bidirectional"))
      (node (ref "J2") (pin "1") (pinfunction "1_1") (pintype "passive"))
      (node (ref "J2") (pin "6") (pinfunction "1_6") (pintype "passive"))
    )
    (net (code "8") (name "A0") (class "Default")
      (node (ref "J9") (pin "5") (pinfunction "5_5") (pintype "passive"))
      (node (ref "U1") (pin "23") (pinfunction "PC0(ADC0)_23") (pintype "bidirectional"))
    )
    (net (code "9") (name "A1") (class "Default")
      (node (ref "J9") (pin "8") (pinfunction "8_8") (pintype "passive"))
      (node (ref "U1") (pin "24") (pinfunction "PC1(ADC1)_24") (pintype "bidirectional"))
    )
    (net (code "10") (name "A2") (class "Default")
      (node (ref "J9") (pin "6") (pinfunction "6_6") (pintype "passive"))
      (node (ref "U1") (pin "25") (pinfunction "PC2(ADC2)_25") (pintype "bidirectional"))
    )
    (net (code "11") (name "A3") (class "Default")
      (node (ref "J9") (pin "4") (pinfunction "4_4") (pintype "passive"))
      (node (ref "U1") (pin "26") (pinfunction "PC3(ADC3)_26") (pintype "bidirectional"))
    )
    (net (code "12") (name "A6") (class "Default")
      (node (ref "U1") (pin "19") (pinfunction "ADC6_19") (pintype "bidirectional"))
    )
    (net (code "13") (name "A7") (class "Default")
      (node (ref "U1") (pin "22") (pinfunction "ADC7_22") (pintype "bidirectional"))
    )
    (net (code "14") (name "CE") (class "Default")
      (node (ref "R13") (pin "1") (pinfunction "1_1") (pintype "passive"))
      (node (ref "R2") (pin "4") (pinfunction "1_4") (pintype "passive"))
      (node (ref "U1") (pin "13") (pinfunction "PB1(OC1A)_13") (pintype "bidirectional"))
    )
    (net (code "15") (name "CLK") (class "Default")
      (node (ref "R2") (pin "1") (pinfunction "1_1") (pintype "passive"))
      (node (ref "TP2") (pin "TP") (pinfunction "TP_TP") (pintype "input"))
      (node (ref "U1") (pin "17") (pinfunction "PB5(SCK)_17") (pintype "bidirectional"))
    )
    (net (code "16") (name "CP") (class "Default")
      (node (ref "C23") (pin "1") (pinfunction "1_1") (pintype "passive"))
      (node (ref "C24") (pin "1") (pinfunction "1_1") (pintype "passive"))
      (node (ref "IC1") (pin "7") (pinfunction "CP_OUT_7") (pintype "bidirectional"))
      (node (ref "R6") (pin "2") (pinfunction "2_2") (pintype "passive"))
    )
    (net (code "17") (name "D0") (class "Default")
      (node (ref "J8") (pin "2") (pinfunction "2_2") (pintype "passive"))
      (node (ref "U1") (pin "30") (pinfunction "PD0(RXD)_30") (pintype "bidirectional"))
    )
    (net (code "18") (name "D1") (class "Default")
      (node (ref "J8") (pin "3") (pinfunction "3_3") (pintype "passive"))
      (node (ref "U1") (pin "31") (pinfunction "PD1(TXD)_31") (pintype "bidirectional"))
    )
    (net (code "19") (name "D2") (class "Default")
      (node (ref "IC7") (pin "4") (pinfunction "Y_4") (pintype "bidirectional"))
      (node (ref "U1") (pin "32") (pinfunction "PD2(INT0)_32") (pintype "bidirectional"))
    )
    (net (code "20") (name "D3") (class "Default")
      (node (ref "J9") (pin "7") (pinfunction "7_7") (pintype "passive"))
      (node (ref "U1") (pin "1") (pinfunction "PD3(INT1)_1") (pintype "bidirectional"))
    )
    (net (code "21") (name "D4") (class "Default")
      (node (ref "J9") (pin "3") (pinfunction "3_3") (pintype "passive"))
      (node (ref "U1") (pin "2") (pinfunction "PD4(XCK/T0)_2") (pintype "bidirectional"))
    )
    (net (code "22") (name "D5") (class "Default")
      (node (ref "U1") (pin "9") (pinfunction "PD5(T1)_9") (pintype "bidirectional"))
    )
    (net (code "23") (name "D6") (class "Default")
      (node (ref "R20") (pin "2") (pinfunction "2_2") (pintype "passive"))
      (node (ref "U1") (pin "10") (pinfunction "PD6(AIN0)_10") (pintype "bidirectional"))
    )
    (net (code "24") (name "GND") (class "Default")
      (node (ref "AT1") (pin "3") (pinfunction "3_3") (pintype "bidirectional"))
      (node (ref "C1") (pin "2") (pinfunction "2_2") (pintype "passive"))
      (node (ref "C10") (pin "2") (pinfunction "2_2") (pintype "passive"))
      (node (ref "C11") (pin "2") (pinfunction "2_2") (pintype "passive"))
      (node (ref "C12") (pin "2") (pinfunction "2_2") (pintype "passive"))
      (node (ref "C13") (pin "2") (pinfunction "2_2") (pintype "passive"))
      (node (ref "C14") (pin "2") (pinfunction "2_2") (pintype "passive"))
      (node (ref "C15") (pin "2") (pinfunction "2_2") (pintype "passive"))
      (node (ref "C16") (pin "2") (pinfunction "2_2") (pintype "passive"))
      (node (ref "C19") (pin "1") (pinfunction "1_1") (pintype "passive"))
      (node (ref "C2") (pin "2") (pinfunction "2_2") (pintype "passive"))
      (node (ref "C20") (pin "1") (pinfunction "1_1") (pintype "passive"))
      (node (ref "C22") (pin "2") (pinfunction "2_2") (pintype "passive"))
      (node (ref "C24") (pin "2") (pinfunction "2_2") (pintype "passive"))
      (node (ref "C25") (pin "2") (pinfunction "2_2") (pintype "passive"))
      (node (ref "C26") (pin "1") (pinfunction "1_1") (pintype "passive"))
      (node (ref "C27") (pin "1") (pinfunction "1_1") (pintype "passive"))
      (node (ref "C28") (pin "1") (pinfunction "1_1") (pintype "passive"))
      (node (ref "C29") (pin "1") (pinfunction "1_1") (pintype "passive"))
      (node (ref "C3") (pin "2") (pinfunction "2_2") (pintype "passive"))
      (node (ref "C30") (pin "2") (pinfunction "2_2") (pintype "passive"))
      (node (ref "C31") (pin "2") (pinfunction "2_2") (pintype "passive"))
      (node (ref "C32") (pin "2") (pinfunction "2_2") (pintype "passive"))
      (node (ref "C33") (pin "2") (pinfunction "2_2") (pintype "passive"))
      (node (ref "C34") (pin "2") (pinfunction "2_2") (pintype "passive"))
      (node (ref "C35") (pin "2") (pinfunction "2_2") (pintype "passive"))
      (node (ref "C36") (pin "2") (pinfunction "2_2") (pintype "passive"))
      (node (ref "C37") (pin "2") (pinfunction "2_2") (pintype "passive"))
      (node (ref "C38") (pin "2") (pinfunction "2_2") (pintype "passive"))
      (node (ref "C39") (pin "2") (pinfunction "2_2") (pintype "passive"))
      (node (ref "C4") (pin "2") (pinfunction "2_2") (pintype "passive"))
      (node (ref "C41") (pin "2") (pinfunction "2_2") (pintype "passive"))
      (node (ref "C42") (pin "2") (pinfunction "2_2") (pintype "passive"))
      (node (ref "C43") (pin "2") (pinfunction "2_2") (pintype "passive"))
      (node (ref "C5") (pin "2") (pinfunction "2_2") (pintype "passive"))
      (node (ref "C6") (pin "2") (pinfunction "2_2") (pintype "passive"))
      (node (ref "C7") (pin "2") (pinfunction "2_2") (pintype "passive"))
      (node (ref "C8") (pin "2") (pinfunction "2_2") (pintype "passive"))
      (node (ref "C9") (pin "2") (pinfunction "2_2") (pintype "passive"))
      (node (ref "FL1") (pin "1") (pinfunction "GND_1_1") (pintype "bidirectional"))
      (node (ref "FL1") (pin "3") (pinfunction "GND_1_3") (pintype "bidirectional"))
      (node (ref "FL1") (pin "5") (pinfunction "NC_5") (pintype "bidirectional"))
      (node (ref "IC1") (pin "11") (pinfunction "GND_RF_11") (pintype "bidirectional"))
      (node (ref "IC1") (pin "18") (pinfunction "GND_VCO_18") (pintype "bidirectional"))
      (node (ref "IC1") (pin "21") (pinfunction "GND_TUNE_21") (pintype "bidirectional"))
      (node (ref "IC1") (pin "27") (pinfunction "GND_DIG_27") (pintype "bidirectional"))
      (node (ref "IC1") (pin "31") (pinfunction "GND_SD_31") (pintype "bidirectional"))
      (node (ref "IC1") (pin "33") (pinfunction "EP_33") (pintype "bidirectional"))
      (node (ref "IC1") (pin "8") (pinfunction "GND_CP_8") (pintype "bidirectional"))
      (node (ref "IC1") (pin "9") (pinfunction "GND_PLL_9") (pintype "bidirectional"))
      (node (ref "IC2") (pin "4") (pinfunction "GND_4") (pintype "bidirectional"))
      (node (ref "IC3") (pin "4") (pinfunction "GND_4") (pintype "bidirectional"))
      (node (ref "IC4") (pin "5") (pinfunction "GND_5") (pintype "bidirectional"))
      (node (ref "IC6") (pin "1") (pinfunction "GND_1_1") (pintype "bidirectional"))
      (node (ref "IC6") (pin "2") (pinfunction "GND_2_2") (pintype "bidirectional"))
      (node (ref "IC7") (pin "1") (pinfunction "B_1") (pintype "bidirectional"))
      (node (ref "IC7") (pin "2") (pinfunction "GND_2") (pintype "bidirectional"))
      (node (ref "IC7") (pin "6") (pinfunction "C_6") (pintype "bidirectional"))
      (node (ref "J1") (pin "10") (pinfunction "2_10") (pintype "passive"))
      (node (ref "J1") (pin "2") (pinfunction "2_2") (pintype "passive"))
      (node (ref "J1") (pin "3") (pinfunction "2_3") (pintype "passive"))
      (node (ref "J1") (pin "4") (pinfunction "2_4") (pintype "passive"))
      (node (ref "J1") (pin "5") (pinfunction "2_5") (pintype "passive"))
      (node (ref "J1") (pin "7") (pinfunction "2_7") (pintype "passive"))
      (node (ref "J1") (pin "8") (pinfunction "2_8") (pintype "passive"))
      (node (ref "J1") (pin "9") (pinfunction "2_9") (pintype "passive"))
      (node (ref "J2") (pin "10") (pinfunction "2_10") (pintype "passive"))
      (node (ref "J2") (pin "2") (pinfunction "2_2") (pintype "passive"))
      (node (ref "J2") (pin "3") (pinfunction "2_3") (pintype "passive"))
      (node (ref "J2") (pin "4") (pinfunction "2_4") (pintype "passive"))
      (node (ref "J2") (pin "5") (pinfunction "2_5") (pintype "passive"))
      (node (ref "J2") (pin "7") (pinfunction "2_7") (pintype "passive"))
      (node (ref "J2") (pin "8") (pinfunction "2_8") (pintype "passive"))
      (node (ref "J2") (pin "9") (pinfunction "2_9") (pintype "passive"))
      (node (ref "J3") (pin "10") (pinfunction "2_10") (pintype "passive"))
      (node (ref "J3") (pin "2") (pinfunction "2_2") (pintype "passive"))
      (node (ref "J3") (pin "3") (pinfunction "2_3") (pintype "passive"))
      (node (ref "J3") (pin "4") (pinfunction "2_4") (pintype "passive"))
      (node (ref "J3") (pin "5") (pinfunction "2_5") (pintype "passive"))
      (node (ref "J3") (pin "7") (pinfunction "2_7") (pintype "passive"))
      (node (ref "J3") (pin "8") (pinfunction "2_8") (pintype "passive"))
      (node (ref "J3") (pin "9") (pinfunction "2_9") (pintype "passive"))
      (node (ref "J6") (pin "10") (pinfunction "2_10") (pintype "passive"))
      (node (ref "J6") (pin "2") (pinfunction "2_2") (pintype "passive"))
      (node (ref "J6") (pin "3") (pinfunction "2_3") (pintype "passive"))
      (node (ref "J6") (pin "4") (pinfunction "2_4") (pintype "passive"))
      (node (ref "J6") (pin "5") (pinfunction "2_5") (pintype "passive"))
      (node (ref "J6") (pin "7") (pinfunction "2_7") (pintype "passive"))
      (node (ref "J6") (pin "8") (pinfunction "2_8") (pintype "passive"))
      (node (ref "J6") (pin "9") (pinfunction "2_9") (pintype "passive"))
      (node (ref "J7") (pin "10") (pinfunction "2_10") (pintype "passive"))
      (node (ref "J7") (pin "2") (pinfunction "2_2") (pintype "passive"))
      (node (ref "J7") (pin "3") (pinfunction "2_3") (pintype "passive"))
      (node (ref "J7") (pin "4") (pinfunction "2_4") (pintype "passive"))
      (node (ref "J7") (pin "5") (pinfunction "2_5") (pintype "passive"))
      (node (ref "J7") (pin "7") (pinfunction "2_7") (pintype "passive"))
      (node (ref "J7") (pin "8") (pinfunction "2_8") (pintype "passive"))
      (node (ref "J7") (pin "9") (pinfunction "2_9") (pintype "passive"))
      (node (ref "J9") (pin "10") (pinfunction "10_10") (pintype "passive"))
      (node (ref "J9") (pin "2") (pinfunction "2_2") (pintype "passive"))
      (node (ref "J9") (pin "9") (pinfunction "9_9") (pintype "passive"))
      (node (ref "LED1") (pin "C") (pinfunction "C_C") (pintype "passive"))
      (node (ref "Q8") (pin "2") (pinfunction "S_2") (pintype "passive"))
      (node (ref "R1") (pin "2") (pinfunction "2_2") (pintype "passive"))
      (node (ref "R23") (pin "1") (pinfunction "1_1") (pintype "passive"))
      (node (ref "R8") (pin "1") (pinfunction "1_1") (pintype "passive"))
      (node (ref "TP6") (pin "TP") (pinfunction "TP_TP") (pintype "input"))
      (node (ref "U$1") (pin "P$1") (pinfunction "P$1_P$1") (pintype "bidirectional"))
      (node (ref "U$1") (pin "P$10") (pinfunction "P$1_P$10") (pintype "bidirectional"))
      (node (ref "U$1") (pin "P$11") (pinfunction "P$1_P$11") (pintype "bidirectional"))
      (node (ref "U$1") (pin "P$12") (pinfunction "P$1_P$12") (pintype "bidirectional"))
      (node (ref "U$1") (pin "P$13") (pinfunction "P$1_P$13") (pintype "bidirectional"))
      (node (ref "U$1") (pin "P$14") (pinfunction "P$1_P$14") (pintype "bidirectional"))
      (node (ref "U$1") (pin "P$15") (pinfunction "P$1_P$15") (pintype "bidirectional"))
      (node (ref "U$1") (pin "P$16") (pinfunction "P$1_P$16") (pintype "bidirectional"))
      (node (ref "U$1") (pin "P$2") (pinfunction "P$1_P$2") (pintype "bidirectional"))
      (node (ref "U$1") (pin "P$3") (pinfunction "P$1_P$3") (pintype "bidirectional"))
      (node (ref "U$1") (pin "P$4") (pinfunction "P$1_P$4") (pintype "bidirectional"))
      (node (ref "U$1") (pin "P$5") (pinfunction "P$1_P$5") (pintype "bidirectional"))
      (node (ref "U$1") (pin "P$6") (pinfunction "P$1_P$6") (pintype "bidirectional"))
      (node (ref "U$1") (pin "P$7") (pinfunction "P$1_P$7") (pintype "bidirectional"))
      (node (ref "U$1") (pin "P$8") (pinfunction "P$1_P$8") (pintype "bidirectional"))
      (node (ref "U$1") (pin "P$9") (pinfunction "P$1_P$9") (pintype "bidirectional"))
      (node (ref "U1") (pin "21") (pinfunction "AGND_21") (pintype "bidirectional"))
      (node (ref "U1") (pin "3") (pinfunction "GND_3") (pintype "bidirectional"))
      (node (ref "U1") (pin "5") (pinfunction "GND_5") (pintype "bidirectional"))
      (node (ref "Y1") (pin "2") (pinfunction "GND_1_2") (pintype "bidirectional"))
      (node (ref "Y1") (pin "4") (pinfunction "GND_1_4") (pintype "bidirectional"))
    )
    (net (code "25") (name "GNDIN") (class "Default")
      (node (ref "J8") (pin "6") (pinfunction "6_6") (pintype "passive"))
      (node (ref "J8") (pin "8") (pinfunction "8_8") (pintype "passive"))
      (node (ref "J8") (pin "9") (pinfunction "9_9") (pintype "passive"))
      (node (ref "Q8") (pin "3") (pinfunction "D_3") (pintype "passive"))
    )
    (net (code "26") (name "LD") (class "Default")
      (node (ref "IC1") (pin "25") (pinfunction "LD_25") (pintype "bidirectional"))
      (node (ref "U1") (pin "12") (pinfunction "PB0(ICP)_12") (pintype "bidirectional"))
    )
    (net (code "27") (name "LE") (class "Default")
      (node (ref "R14") (pin "1") (pinfunction "1_1") (pintype "passive"))
      (node (ref "R2") (pin "3") (pinfunction "1_3") (pintype "passive"))
      (node (ref "U1") (pin "14") (pinfunction "PB2(SS/OC1B)_14") (pintype "bidirectional"))
    )
    (net (code "28") (name "MISO") (class "Default")
      (node (ref "JP1") (pin "1") (pinfunction "1_1") (pintype "passive"))
      (node (ref "TP1") (pin "TP") (pinfunction "TP_TP") (pintype "input"))
      (node (ref "U1") (pin "16") (pinfunction "PB4(MISO)_16") (pintype "bidirectional"))
    )
    (net (code "29") (name "MOSI") (class "Default")
      (node (ref "R2") (pin "2") (pinfunction "1_2") (pintype "passive"))
      (node (ref "TP5") (pin "TP") (pinfunction "TP_TP") (pintype "input"))
      (node (ref "U1") (pin "15") (pinfunction "PB3(MOSI/OC2)_15") (pintype "bidirectional"))
    )
    (net (code "30") (name "MUX_OUT") (class "Default")
      (node (ref "IC1") (pin "30") (pinfunction "MUX_OUT_30") (pintype "bidirectional"))
      (node (ref "JP1") (pin "2") (pinfunction "2_2") (pintype "passive"))
    )
    (net (code "31") (name "Net-(C23-Pad2)") (class "Default")
      (node (ref "C23") (pin "2") (pinfunction "2_2") (pintype "passive"))
      (node (ref "R7") (pin "2") (pinfunction "2_2") (pintype "passive"))
    )
    (net (code "32") (name "Net-(FL1-BALANCED_PORT_1)") (class "Default")
      (node (ref "C18") (pin "2") (pinfunction "2_2") (pintype "passive"))
      (node (ref "FL1") (pin "4") (pinfunction "BALANCED_PORT_1_4") (pintype "bidirectional"))
    )
    (net (code "33") (name "Net-(FL1-BALANCED_PORT_2)") (class "Default")
      (node (ref "C17") (pin "2") (pinfunction "2_2") (pintype "passive"))
      (node (ref "FL1") (pin "6") (pinfunction "BALANCED_PORT_2_6") (pintype "bidirectional"))
    )
    (net (code "34") (name "Net-(FL1-UNBALANCED)") (class "Default")
      (node (ref "AT1") (pin "1") (pinfunction "1_1") (pintype "bidirectional"))
      (node (ref "FL1") (pin "2") (pinfunction "UNBALANCED_2") (pintype "bidirectional"))
    )
    (net (code "35") (name "Net-(IC1-BIAS_FILT)") (class "Default")
      (node (ref "C3") (pin "1") (pinfunction "1_1") (pintype "passive"))
      (node (ref "C4") (pin "1") (pinfunction "1_1") (pintype "passive"))
      (node (ref "IC1") (pin "23") (pinfunction "BIAS_FILT_23") (pintype "bidirectional"))
    )
    (net (code "36") (name "Net-(IC1-CE)") (class "Default")
      (node (ref "IC1") (pin "4") (pinfunction "CE_4") (pintype "bidirectional"))
      (node (ref "R2") (pin "5") (pinfunction "2_5") (pintype "passive"))
    )
    (net (code "37") (name "Net-(IC1-CLK)") (class "Default")
      (node (ref "IC1") (pin "1") (pinfunction "CLK_1") (pintype "bidirectional"))
      (node (ref "R2") (pin "8") (pinfunction "2_8") (pintype "passive"))
    )
    (net (code "38") (name "Net-(IC1-DATA)") (class "Default")
      (node (ref "IC1") (pin "2") (pinfunction "DATA_2") (pintype "bidirectional"))
      (node (ref "R2") (pin "7") (pinfunction "2_7") (pintype "passive"))
    )
    (net (code "39") (name "Net-(IC1-LE)") (class "Default")
      (node (ref "IC1") (pin "3") (pinfunction "LE_3") (pintype "bidirectional"))
      (node (ref "R2") (pin "6") (pinfunction "2_6") (pintype "passive"))
    )
    (net (code "40") (name "Net-(IC1-NOISE_FILT)") (class "Default")
      (node (ref "C1") (pin "1") (pinfunction "1_1") (pintype "passive"))
      (node (ref "C2") (pin "1") (pinfunction "1_1") (pintype "passive"))
      (node (ref "IC1") (pin "19") (pinfunction "NOISE_FILT_19") (pintype "bidirectional"))
    )
    (net (code "41") (name "Net-(IC1-REG)") (class "Default")
      (node (ref "C5") (pin "1") (pinfunction "1_1") (pintype "passive"))
      (node (ref "C6") (pin "1") (pinfunction "1_1") (pintype "passive"))
      (node (ref "IC1") (pin "24") (pinfunction "REG_24") (pintype "bidirectional"))
    )
    (net (code "42") (name "Net-(IC1-RFOUTA_N)") (class "Default")
      (node (ref "C18") (pin "1") (pinfunction "1_1") (pintype "passive"))
      (node (ref "IC1") (pin "13") (pinfunction "RFOUTA_N_13") (pintype "bidirectional"))
      (node (ref "R5") (pin "2") (pinfunction "2_2") (pintype "passive"))
    )
    (net (code "43") (name "Net-(IC1-RFOUTA_P)") (class "Default")
      (node (ref "C17") (pin "1") (pinfunction "1_1") (pintype "passive"))
      (node (ref "IC1") (pin "12") (pinfunction "RFOUTA_P_12") (pintype "bidirectional"))
      (node (ref "R4") (pin "2") (pinfunction "2_2") (pintype "passive"))
    )
    (net (code "44") (name "Net-(IC1-RFOUT_EN)") (class "Default")
      (node (ref "IC1") (pin "26") (pinfunction "RFOUT_EN_26") (pintype "bidirectional"))
      (node (ref "R21") (pin "2") (pinfunction "2_2") (pintype "passive"))
    )
    (net (code "45") (name "Net-(IC1-RSET)") (class "Default")
      (node (ref "IC1") (pin "22") (pinfunction "RSET_22") (pintype "bidirectional"))
      (node (ref "R1") (pin "1") (pinfunction "1_1") (pintype "passive"))
    )
    (net (code "46") (name "Net-(IC1-TUNE)") (class "Default")
      (node (ref "C22") (pin "1") (pinfunction "1_1") (pintype "passive"))
      (node (ref "IC1") (pin "20") (pinfunction "TUNE_20") (pintype "bidirectional"))
      (node (ref "R6") (pin "1") (pinfunction "1_1") (pintype "passive"))
    )
    (net (code "47") (name "Net-(IC2-1G)") (class "Default")
      (node (ref "IC2") (pin "2") (pinfunction "1G_2") (pintype "bidirectional"))
      (node (ref "R16") (pin "1") (pinfunction "1_1") (pintype "passive"))
    )
    (net (code "48") (name "Net-(IC2-VDD)") (class "Default")
      (node (ref "C34") (pin "1") (pinfunction "1_1") (pintype "passive"))
      (node (ref "C35") (pin "1") (pinfunction "1_1") (pintype "passive"))
      (node (ref "IC2") (pin "6") (pinfunction "VDD_6") (pintype "bidirectional"))
      (node (ref "L1") (pin "2") (pinfunction "2_2") (pintype "passive"))
      (node (ref "R16") (pin "2") (pinfunction "2_2") (pintype "passive"))
    )
    (net (code "49") (name "Net-(IC3-1G)") (class "Default")
      (node (ref "IC3") (pin "2") (pinfunction "1G_2") (pintype "bidirectional"))
      (node (ref "R15") (pin "1") (pinfunction "1_1") (pintype "passive"))
    )
    (net (code "50") (name "Net-(IC3-CLKIN)") (class "Default")
      (node (ref "C40") (pin "2") (pinfunction "2_2") (pintype "passive"))
      (node (ref "IC3") (pin "1") (pinfunction "CLKIN_1") (pintype "bidirectional"))
      (node (ref "R23") (pin "2") (pinfunction "2_2") (pintype "passive"))
      (node (ref "R24") (pin "1") (pinfunction "1_1") (pintype "passive"))
    )
    (net (code "51") (name "Net-(IC3-VDD)") (class "Default")
      (node (ref "C31") (pin "1") (pinfunction "1_1") (pintype "passive"))
      (node (ref "C32") (pin "1") (pinfunction "1_1") (pintype "passive"))
      (node (ref "IC3") (pin "6") (pinfunction "VDD_6") (pintype "bidirectional"))
      (node (ref "L2") (pin "2") (pinfunction "2_2") (pintype "passive"))
      (node (ref "R15") (pin "2") (pinfunction "2_2") (pintype "passive"))
    )
    (net (code "52") (name "Net-(IC4-EN)") (class "Default")
      (node (ref "C36") (pin "1") (pinfunction "1_1") (pintype "passive"))
      (node (ref "C38") (pin "1") (pinfunction "1_1") (pintype "passive"))
      (node (ref "IC4") (pin "4") (pinfunction "EN_4") (pintype "bidirectional"))
      (node (ref "IC4") (pin "6") (pinfunction "IN_6") (pintype "bidirectional"))
      (node (ref "L3") (pin "2") (pinfunction "2_2") (pintype "passive"))
    )
    (net (code "53") (name "Net-(IC4-PG)") (class "Default")
      (node (ref "IC4") (pin "3") (pinfunction "PG_3") (pintype "bidirectional"))
      (node (ref "R19") (pin "1") (pinfunction "1_1") (pintype "passive"))
    )
    (net (code "54") (name "Net-(IC6-VREF)") (class "Default")
      (node (ref "C43") (pin "1") (pinfunction "1_1") (pintype "passive"))
      (node (ref "IC6") (pin "6") (pinfunction "VREF_6") (pintype "bidirectional"))
      (node (ref "R24") (pin "2") (pinfunction "2_2") (pintype "passive"))
    )
    (net (code "55") (name "Net-(LED1-PadA)") (class "Default")
      (node (ref "LED1") (pin "A") (pinfunction "A_A") (pintype "passive"))
      (node (ref "R20") (pin "1") (pinfunction "1_1") (pintype "passive"))
    )
    (net (code "56") (name "Net-(U1-PB6(XTAL1{slash}TOSC1))") (class "Default")
      (node (ref "C26") (pin "2") (pinfunction "2_2") (pintype "passive"))
      (node (ref "U1") (pin "7") (pinfunction "PB6(XTAL1/TOSC1)_7") (pintype "bidirectional"))
      (node (ref "Y1") (pin "3") (pinfunction "X2_3") (pintype "bidirectional"))
    )
    (net (code "57") (name "Net-(U1-PB7(XTAL2{slash}TOSC2))") (class "Default")
      (node (ref "C27") (pin "2") (pinfunction "2_2") (pintype "passive"))
      (node (ref "U1") (pin "8") (pinfunction "PB7(XTAL2/TOSC2)_8") (pintype "bidirectional"))
      (node (ref "Y1") (pin "1") (pinfunction "X1_1") (pintype "bidirectional"))
    )
    (net (code "58") (name "PPS_IN") (class "Default")
      (node (ref "IC2") (pin "1") (pinfunction "CLKIN_1") (pintype "bidirectional"))
      (node (ref "J6") (pin "1") (pinfunction "1_1") (pintype "passive"))
      (node (ref "J6") (pin "6") (pinfunction "1_6") (pintype "passive"))
    )
    (net (code "59") (name "PPS_PLL") (class "Default")
      (node (ref "IC2") (pin "3") (pinfunction "Y0_3") (pintype "bidirectional"))
      (node (ref "JP1") (pin "3") (pinfunction "3_3") (pintype "passive"))
    )
    (net (code "60") (name "PPS_RPI") (class "Default")
      (node (ref "IC2") (pin "5") (pinfunction "Y2_5") (pintype "bidirectional"))
      (node (ref "IC7") (pin "3") (pinfunction "A_3") (pintype "bidirectional"))
      (node (ref "J8") (pin "7") (pinfunction "7_7") (pintype "passive"))
    )
    (net (code "61") (name "PPS_USRP") (class "Default")
      (node (ref "IC2") (pin "8") (pinfunction "Y1_8") (pintype "bidirectional"))
      (node (ref "J1") (pin "1") (pinfunction "1_1") (pintype "passive"))
      (node (ref "J1") (pin "6") (pinfunction "1_6") (pintype "passive"))
    )
    (net (code "62") (name "RESET") (class "Default")
      (node (ref "R12") (pin "1") (pinfunction "1_1") (pintype "passive"))
      (node (ref "TP3") (pin "TP") (pinfunction "TP_TP") (pintype "input"))
      (node (ref "U1") (pin "29") (pinfunction "PC6(/RESET)_29") (pintype "bidirectional"))
    )
    (net (code "63") (name "RFOUT_EN") (class "Default")
      (node (ref "R21") (pin "1") (pinfunction "1_1") (pintype "passive"))
      (node (ref "U1") (pin "11") (pinfunction "PD7(AIN1)_11") (pintype "bidirectional"))
    )
    (net (code "64") (name "RF_OUT") (class "Default")
      (node (ref "AT1") (pin "2") (pinfunction "2_2") (pintype "bidirectional"))
      (node (ref "J3") (pin "1") (pinfunction "1_1") (pintype "passive"))
      (node (ref "J3") (pin "6") (pinfunction "1_6") (pintype "passive"))
    )
    (net (code "65") (name "SCL") (class "Default")
      (node (ref "J8") (pin "5") (pinfunction "5_5") (pintype "passive"))
      (node (ref "R18") (pin "1") (pinfunction "1_1") (pintype "passive"))
      (node (ref "U1") (pin "28") (pinfunction "PC5(ADC5/SCL)_28") (pintype "bidirectional"))
    )
    (net (code "66") (name "SDA") (class "Default")
      (node (ref "J8") (pin "4") (pinfunction "4_4") (pintype "passive"))
      (node (ref "R17") (pin "1") (pinfunction "1_1") (pintype "passive"))
      (node (ref "U1") (pin "27") (pinfunction "PC4(ADC4/SDA)_27") (pintype "bidirectional"))
    )
    (net (code "67") (name "SW") (class "Default")
      (node (ref "IC1") (pin "5") (pinfunction "SW_5") (pintype "bidirectional"))
      (node (ref "R7") (pin "1") (pinfunction "1_1") (pintype "passive"))
      (node (ref "R8") (pin "2") (pinfunction "2_2") (pintype "passive"))
    )
    (net (code "68") (name "unconnected-(IC1-RFOUTB_N-Pad15)") (class "Default")
      (node (ref "IC1") (pin "15") (pinfunction "RFOUTB_N_15") (pintype "bidirectional"))
    )
    (net (code "69") (name "unconnected-(IC1-RFOUTB_P-Pad14)") (class "Default")
      (node (ref "IC1") (pin "14") (pinfunction "RFOUTB_P_14") (pintype "bidirectional"))
    )
    (net (code "70") (name "unconnected-(IC2-NC-Pad7)") (class "Default")
      (node (ref "IC2") (pin "7") (pinfunction "NC_7") (pintype "no_connect"))
    )
    (net (code "71") (name "unconnected-(IC3-NC-Pad7)") (class "Default")
      (node (ref "IC3") (pin "7") (pinfunction "NC_7") (pintype "no_connect"))
    )
    (net (code "72") (name "unconnected-(IC4-EP-Pad7)") (class "Default")
      (node (ref "IC4") (pin "7") (pinfunction "EP_7") (pintype "bidirectional"))
    )
    (net (code "73") (name "unconnected-(IC4-NC-Pad2)") (class "Default")
      (node (ref "IC4") (pin "2") (pinfunction "NC_2") (pintype "no_connect"))
    )
    (net (code "74") (name "unconnected-(IC6-NR-Pad5)") (class "Default")
      (node (ref "IC6") (pin "5") (pinfunction "NR_5") (pintype "bidirectional"))
    )
    (net (code "75") (name "unconnected-(U1-AREF-Pad20)") (class "Default")
      (node (ref "U1") (pin "20") (pinfunction "AREF_20") (pintype "bidirectional"))
    )
  )
)
